# nas.net
KiCad netlist of a schematic drawn in EAGLE
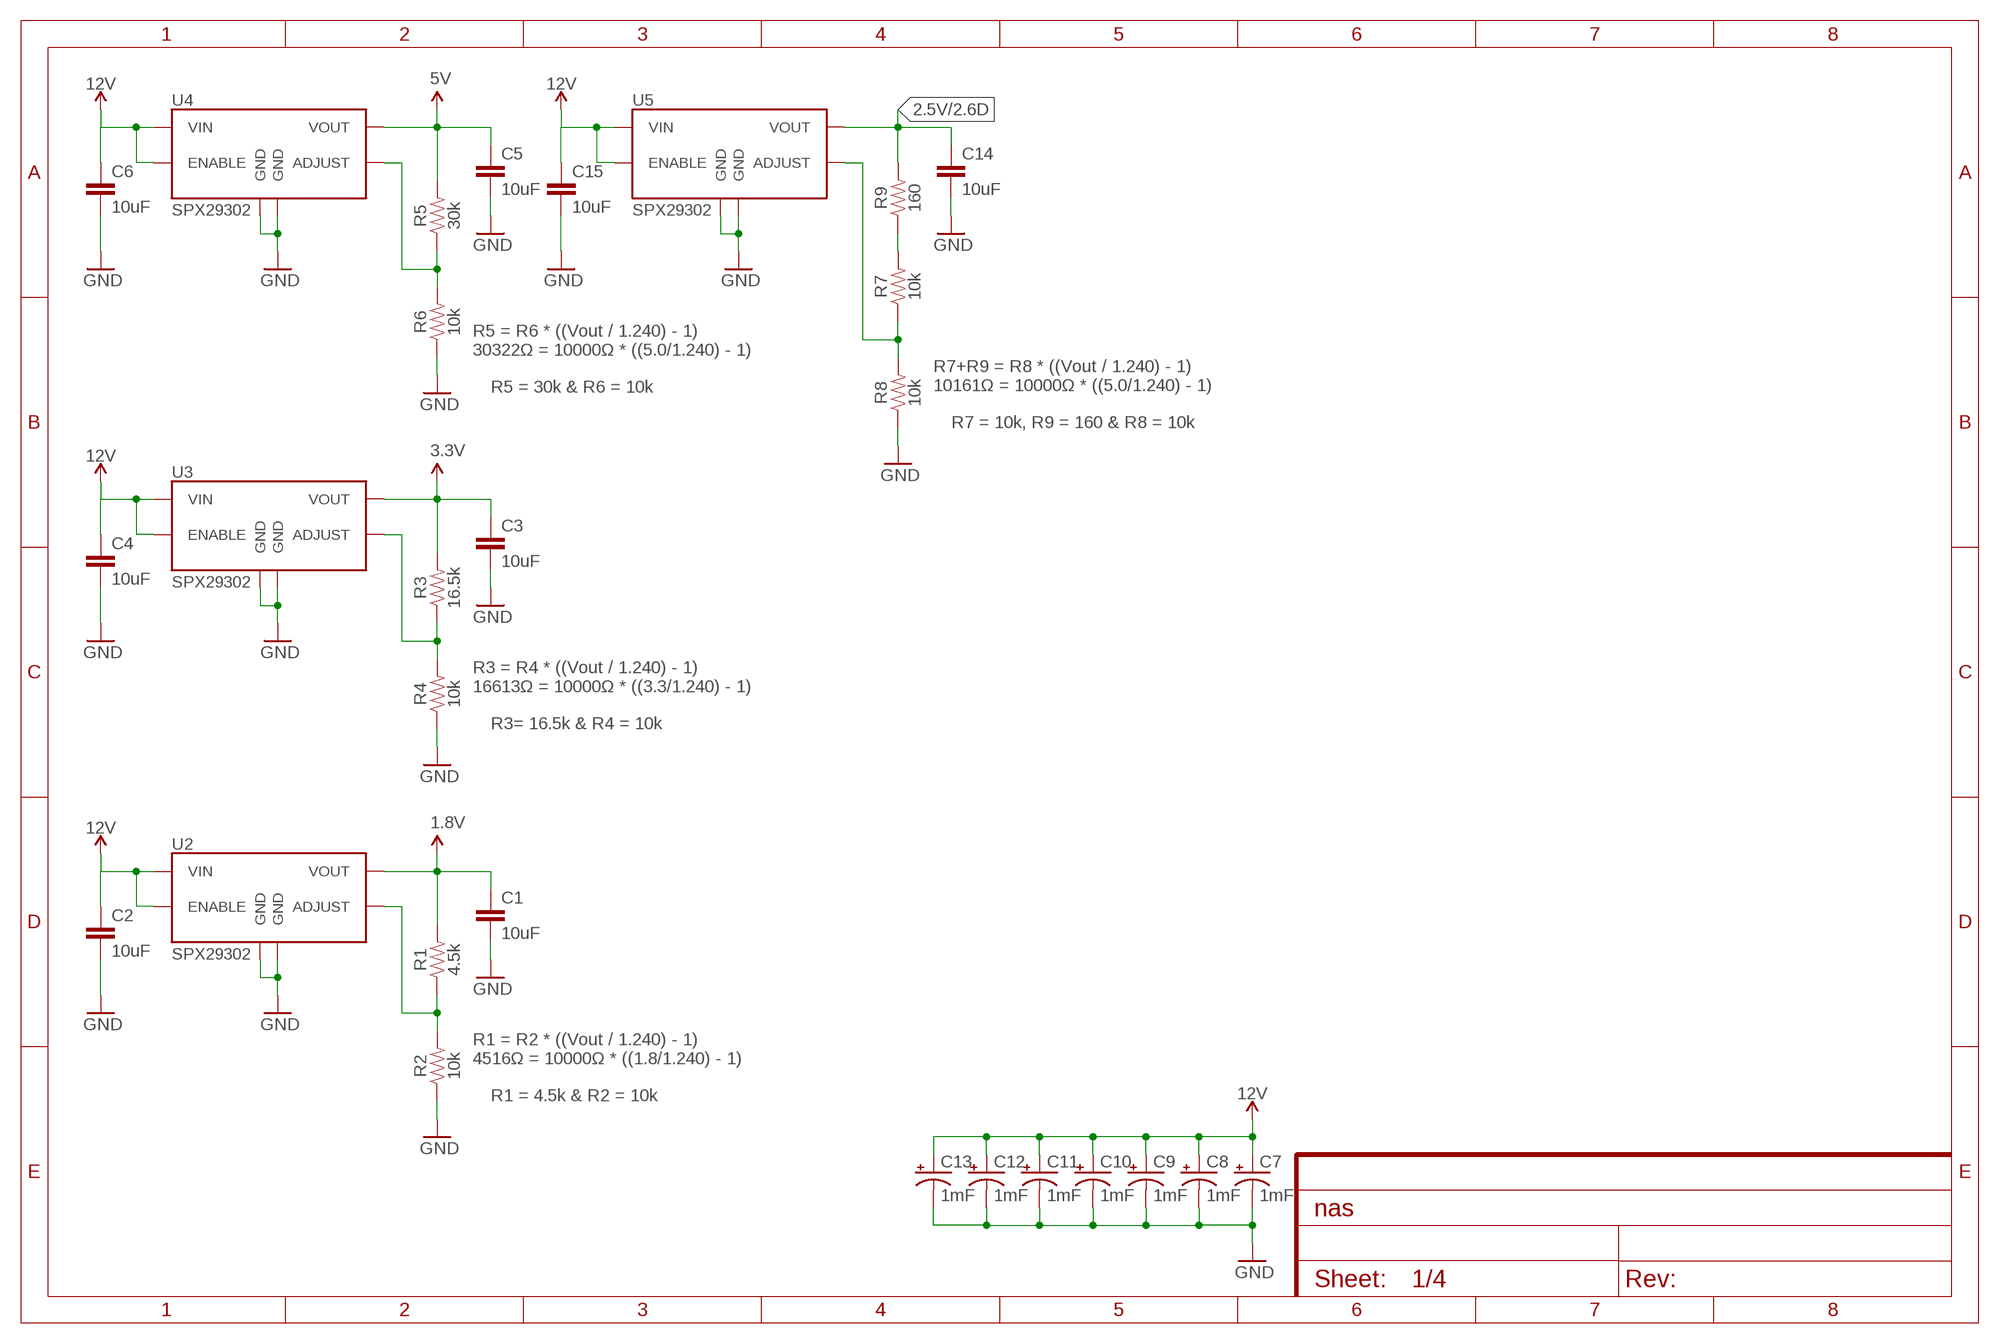
[diagram p0: schematic, sheet 1]
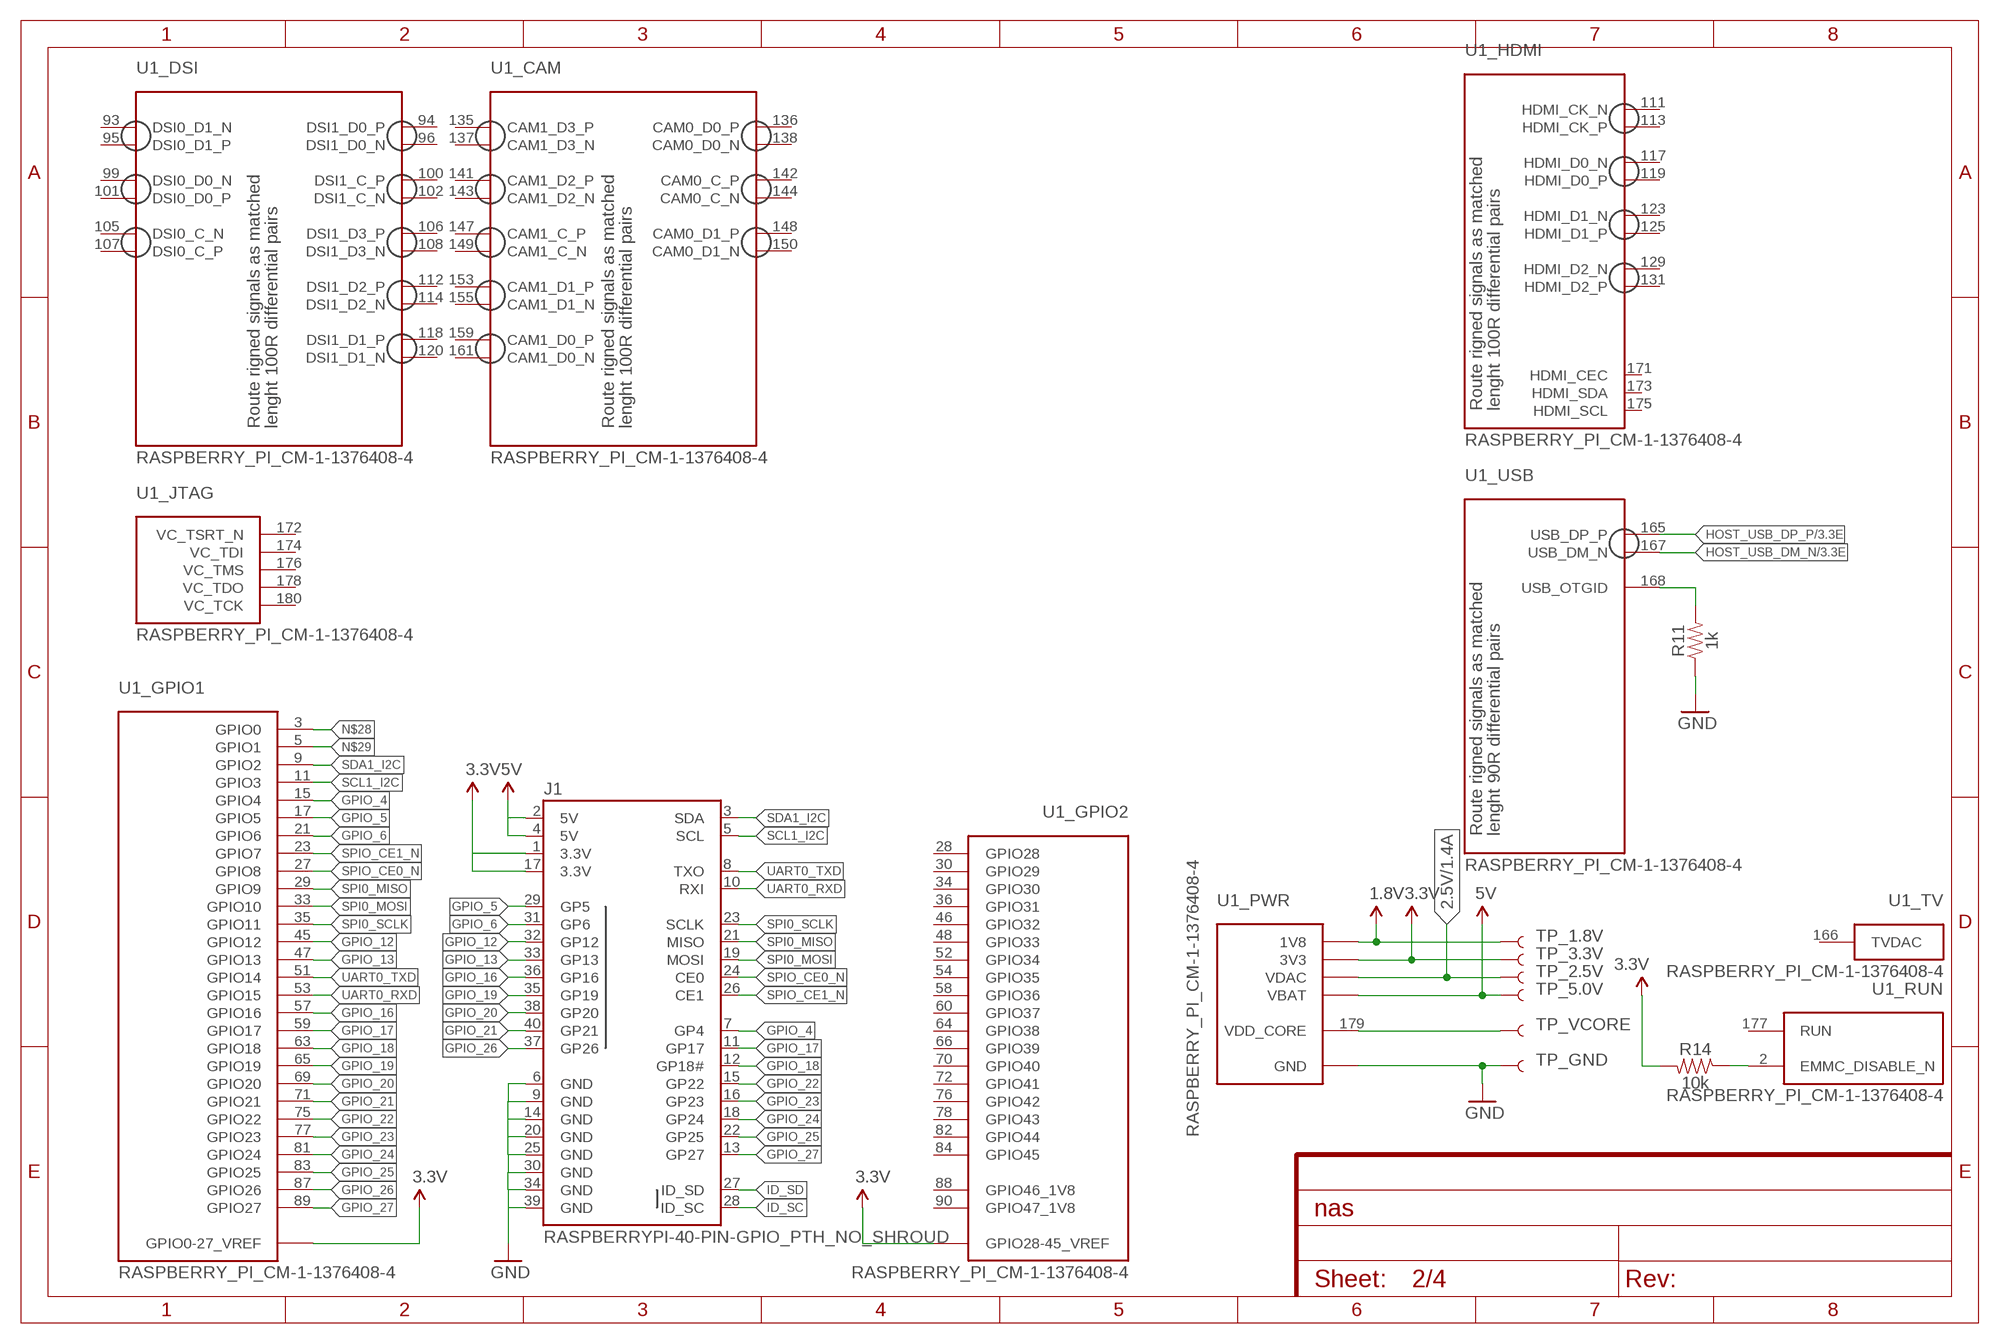
[diagram p1: schematic, sheet 2]
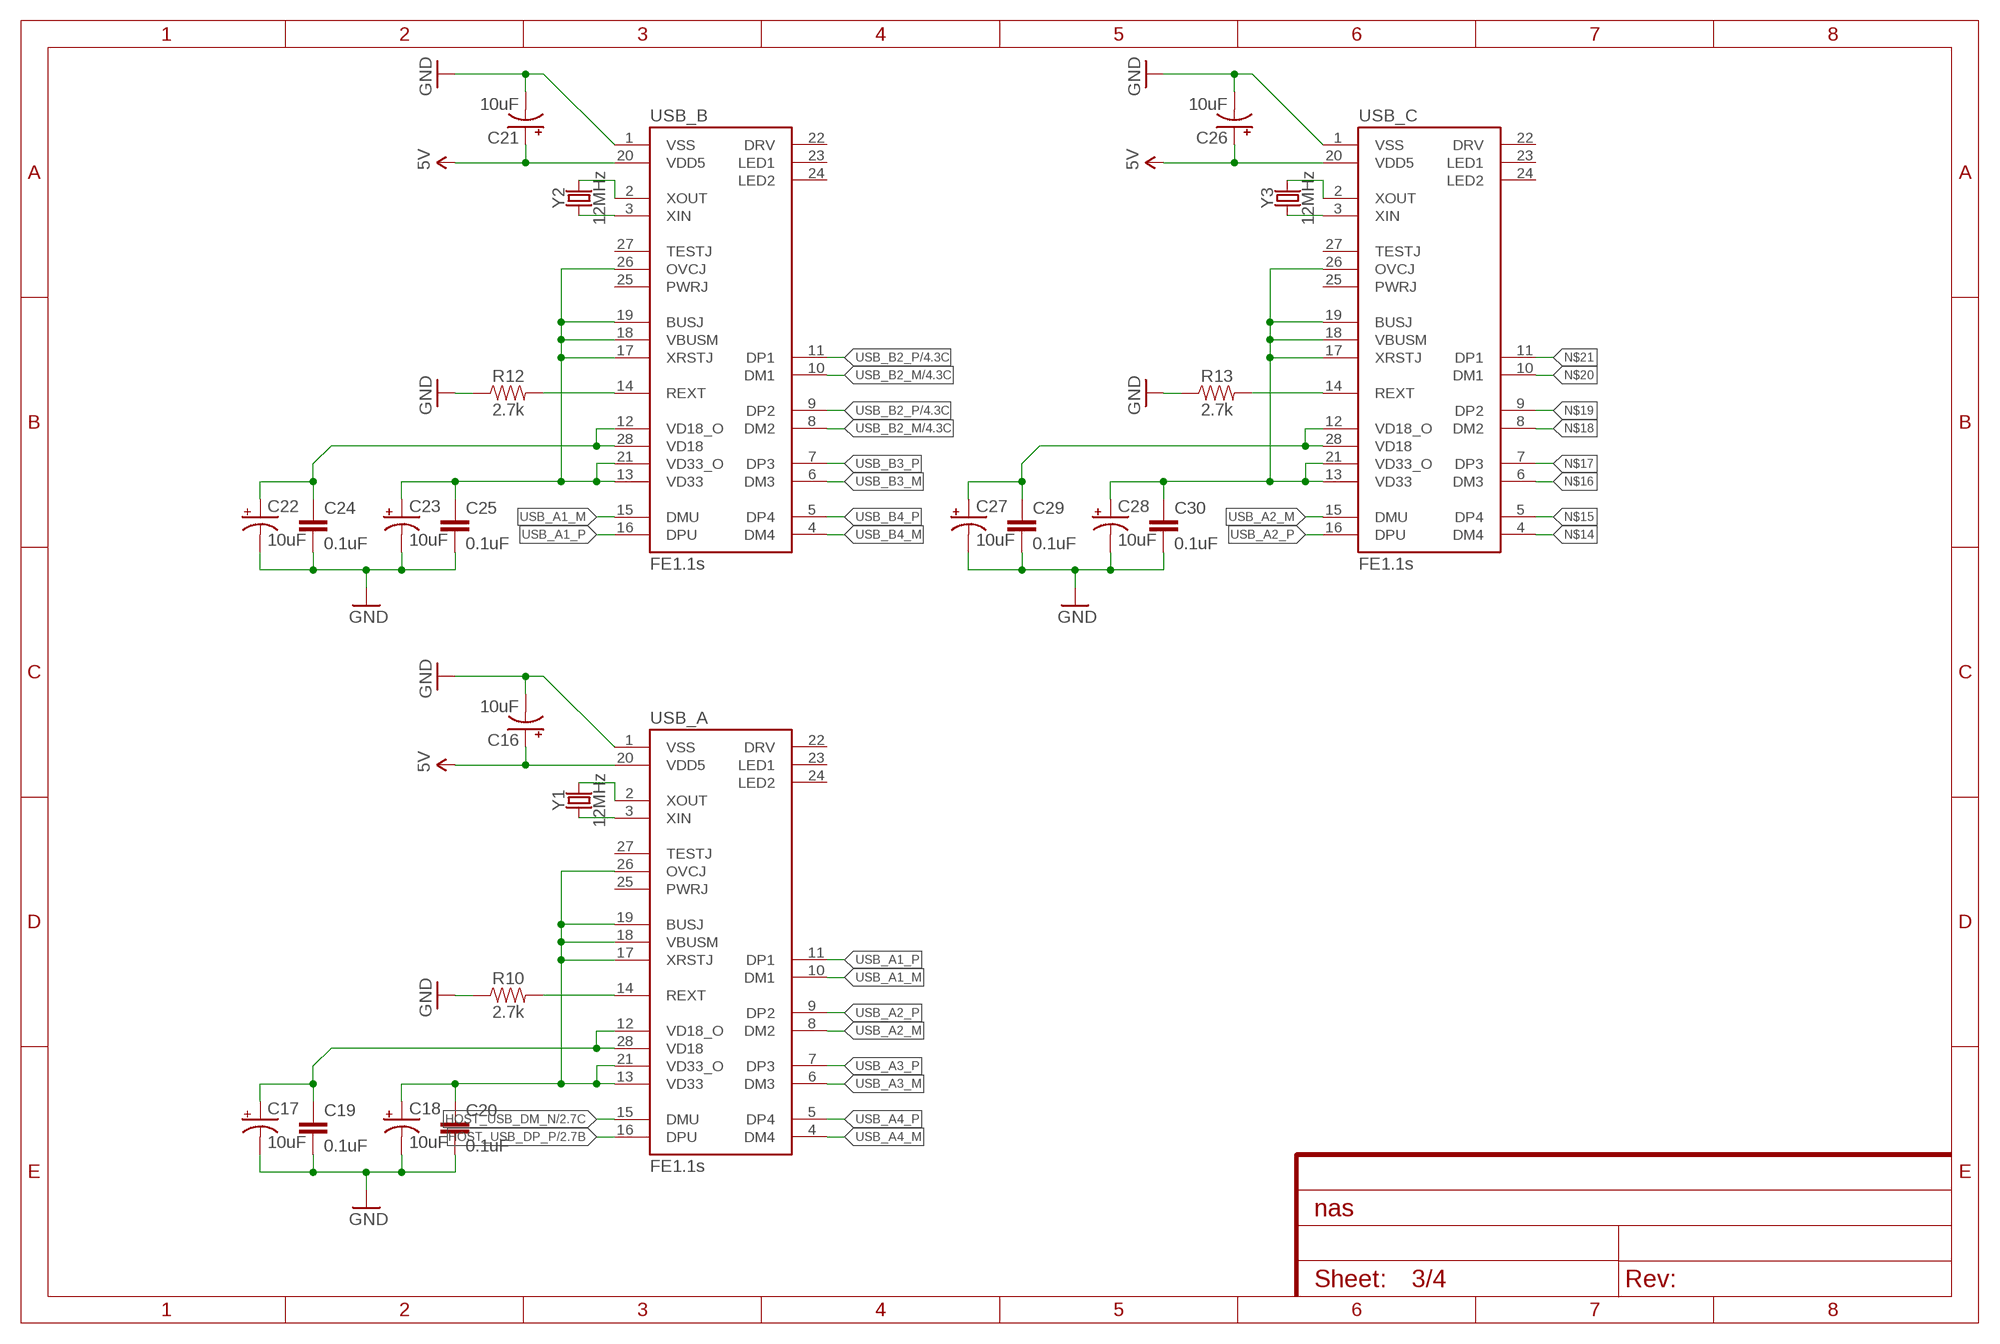
[diagram p2: schematic, sheet 3]
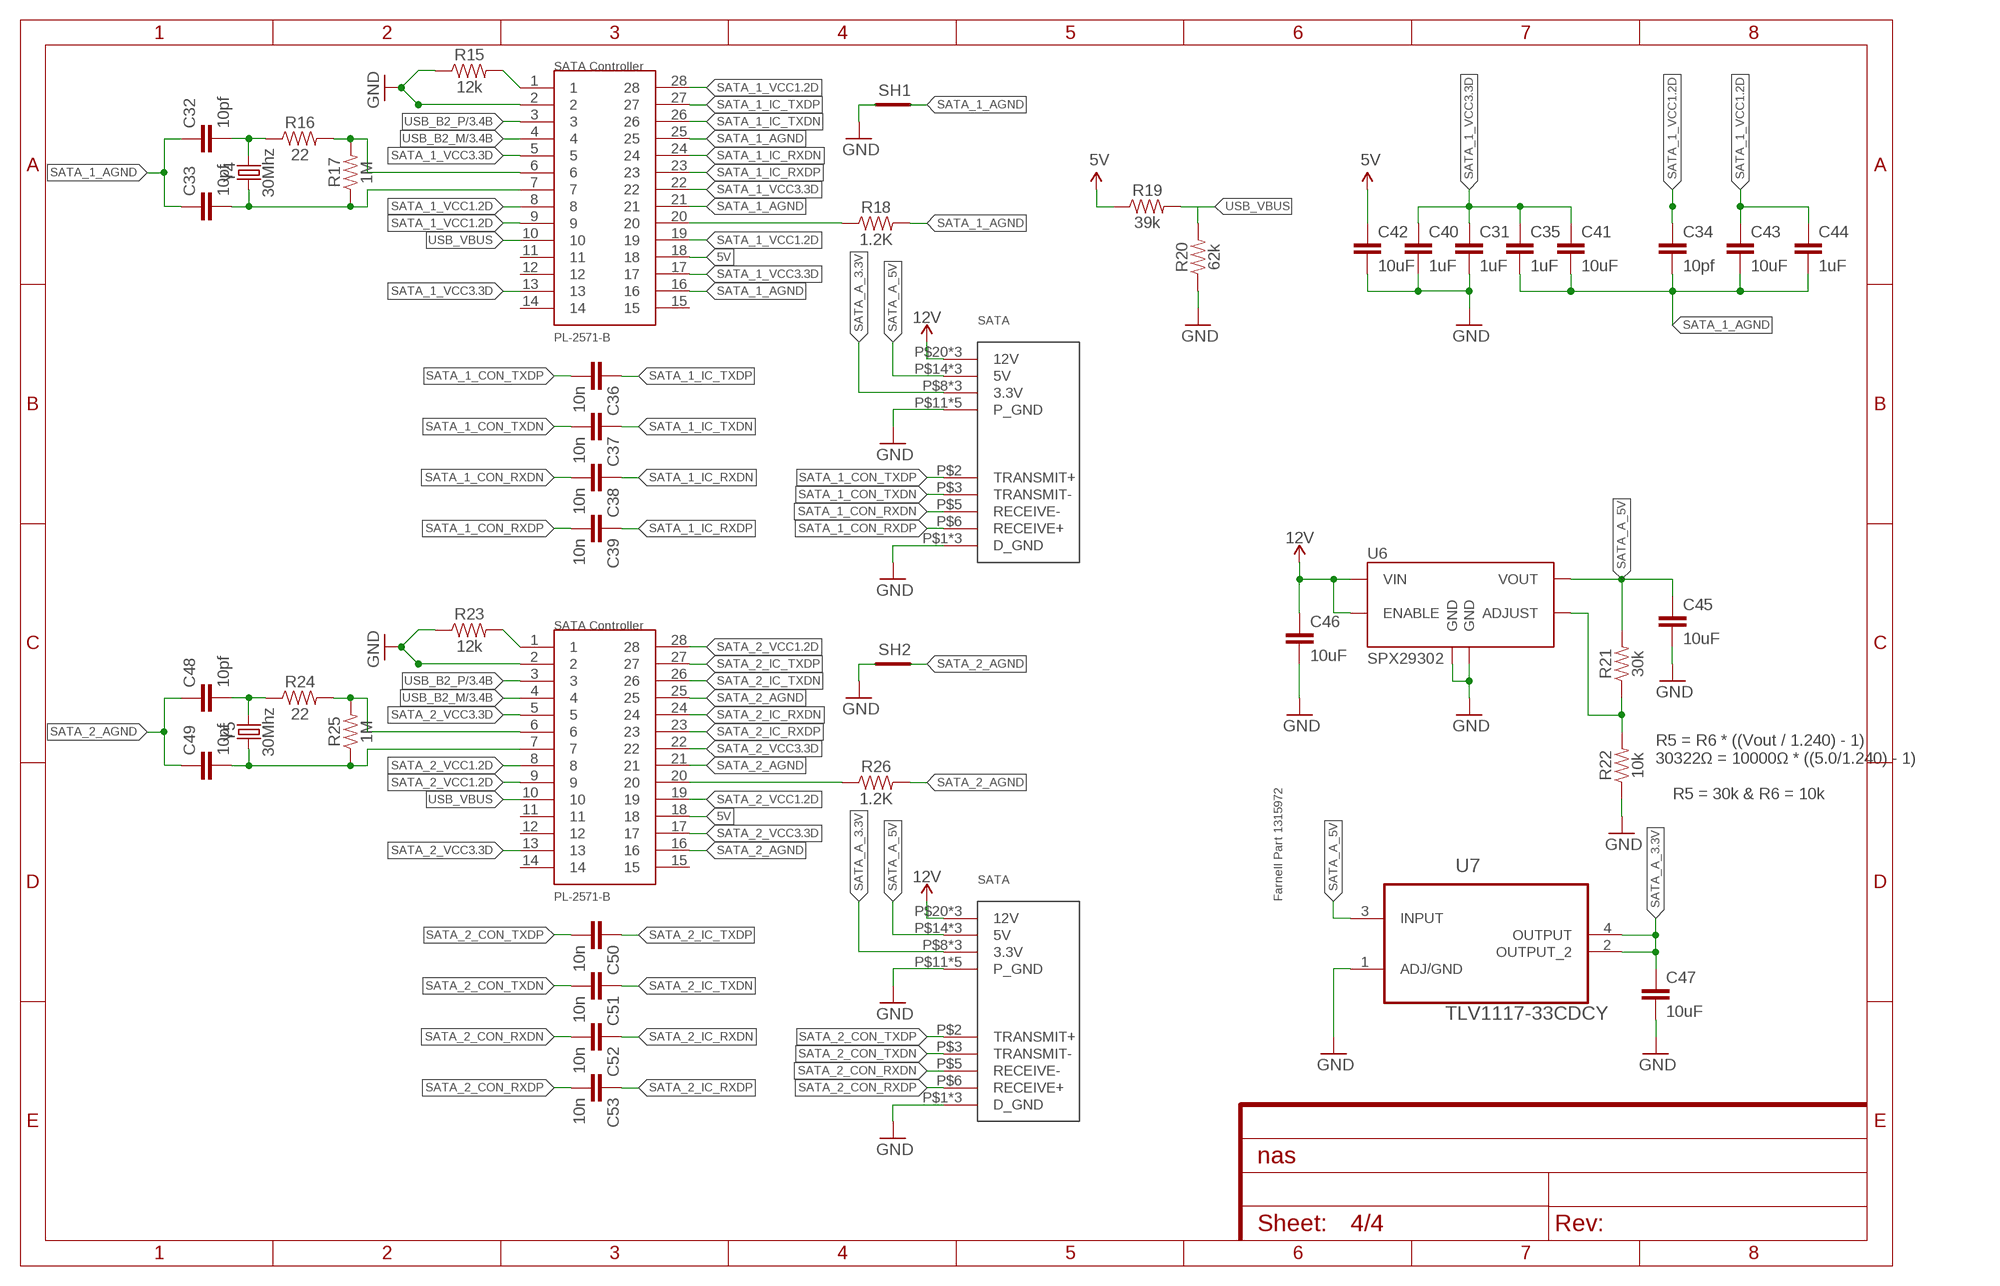
[diagram p3: schematic, sheet 4]

(export (version "E")
  (design (tool "Eeschema 10.0.6"))
  (components
    (comp (ref "J1")
      (value "RASPBERRYPI-40-PIN-GPIO_PTH_NO_SHROUD")
      (footprint "eagle-import:2X20")
      (libsource (lib "eagle-import") (part "RASPBERRYPI-40-PIN-GPIO_PTH_NO_SHROUD"))
    )
    (comp (ref "R11")
      (value "1k")
      (footprint "eagle-import:1206")
      (libsource (lib "eagle-import") (part "RESISTOR1206"))
    )
    (comp (ref "R14")
      (value "10k")
      (footprint "eagle-import:1206")
      (libsource (lib "eagle-import") (part "RESISTOR1206"))
    )
    (comp (ref "TP_1.8V")
      (value "TEST-POINT2")
      (footprint "eagle-import:PAD.02X.02")
      (libsource (lib "eagle-import") (part "TEST-POINT2"))
    )
    (comp (ref "TP_2.5V")
      (value "TEST-POINT2")
      (footprint "eagle-import:PAD.02X.02")
      (libsource (lib "eagle-import") (part "TEST-POINT2"))
    )
    (comp (ref "TP_3.3V")
      (value "TEST-POINT2")
      (footprint "eagle-import:PAD.02X.02")
      (libsource (lib "eagle-import") (part "TEST-POINT2"))
    )
    (comp (ref "TP_5.0V")
      (value "TEST-POINT2")
      (footprint "eagle-import:PAD.02X.02")
      (libsource (lib "eagle-import") (part "TEST-POINT2"))
    )
    (comp (ref "TP_GND")
      (value "TEST-POINT2")
      (footprint "eagle-import:PAD.02X.02")
      (libsource (lib "eagle-import") (part "TEST-POINT2"))
    )
    (comp (ref "TP_VCORE")
      (value "TEST-POINT2")
      (footprint "eagle-import:PAD.02X.02")
      (libsource (lib "eagle-import") (part "TEST-POINT2"))
    )
    (comp (ref "U1")
      (value "RASPBERRY_PI_CM-1-1376408-4")
      (footprint "eagle-import:1-1376408-4")
      (libsource (lib "eagle-import") (part "RASPBERRY_PI_CM-1-1376408-4"))
    )
    (comp (ref "C16")
      (value "10uF")
      (footprint "eagle-import:EIA3216")
      (libsource (lib "eagle-import") (part "10UF-POLAR-EIA3216-16V-10%(TANT)"))
    )
    (comp (ref "C17")
      (value "10uF")
      (footprint "eagle-import:EIA3216")
      (libsource (lib "eagle-import") (part "10UF-POLAR-EIA3216-16V-10%(TANT)"))
    )
    (comp (ref "C18")
      (value "10uF")
      (footprint "eagle-import:EIA3216")
      (libsource (lib "eagle-import") (part "10UF-POLAR-EIA3216-16V-10%(TANT)"))
    )
    (comp (ref "C19")
      (value "0.1uF")
      (footprint "eagle-import:1206")
      (libsource (lib "eagle-import") (part "10UF-1206-6.3V-20%"))
    )
    (comp (ref "C20")
      (value "0.1uF")
      (footprint "eagle-import:1206")
      (libsource (lib "eagle-import") (part "10UF-1206-6.3V-20%"))
    )
    (comp (ref "C21")
      (value "10uF")
      (footprint "eagle-import:EIA3216")
      (libsource (lib "eagle-import") (part "10UF-POLAR-EIA3216-16V-10%(TANT)"))
    )
    (comp (ref "C22")
      (value "10uF")
      (footprint "eagle-import:EIA3216")
      (libsource (lib "eagle-import") (part "10UF-POLAR-EIA3216-16V-10%(TANT)"))
    )
    (comp (ref "C23")
      (value "10uF")
      (footprint "eagle-import:EIA3216")
      (libsource (lib "eagle-import") (part "10UF-POLAR-EIA3216-16V-10%(TANT)"))
    )
    (comp (ref "C24")
      (value "0.1uF")
      (footprint "eagle-import:1206")
      (libsource (lib "eagle-import") (part "10UF-1206-6.3V-20%"))
    )
    (comp (ref "C25")
      (value "0.1uF")
      (footprint "eagle-import:1206")
      (libsource (lib "eagle-import") (part "10UF-1206-6.3V-20%"))
    )
    (comp (ref "C26")
      (value "10uF")
      (footprint "eagle-import:EIA3216")
      (libsource (lib "eagle-import") (part "10UF-POLAR-EIA3216-16V-10%(TANT)"))
    )
    (comp (ref "C27")
      (value "10uF")
      (footprint "eagle-import:EIA3216")
      (libsource (lib "eagle-import") (part "10UF-POLAR-EIA3216-16V-10%(TANT)"))
    )
    (comp (ref "C28")
      (value "10uF")
      (footprint "eagle-import:EIA3216")
      (libsource (lib "eagle-import") (part "10UF-POLAR-EIA3216-16V-10%(TANT)"))
    )
    (comp (ref "C29")
      (value "0.1uF")
      (footprint "eagle-import:1206")
      (libsource (lib "eagle-import") (part "10UF-1206-6.3V-20%"))
    )
    (comp (ref "C30")
      (value "0.1uF")
      (footprint "eagle-import:1206")
      (libsource (lib "eagle-import") (part "10UF-1206-6.3V-20%"))
    )
    (comp (ref "R10")
      (value "2.7k")
      (footprint "eagle-import:1206")
      (libsource (lib "eagle-import") (part "RESISTOR1206"))
    )
    (comp (ref "R12")
      (value "2.7k")
      (footprint "eagle-import:1206")
      (libsource (lib "eagle-import") (part "RESISTOR1206"))
    )
    (comp (ref "R13")
      (value "2.7k")
      (footprint "eagle-import:1206")
      (libsource (lib "eagle-import") (part "RESISTOR1206"))
    )
    (comp (ref "USB_A")
      (value "FE1.1S")
      (footprint "eagle-import:FE1.1S_SSOP-28")
      (libsource (lib "eagle-import") (part "FE1.1S"))
    )
    (comp (ref "USB_B")
      (value "FE1.1S")
      (footprint "eagle-import:FE1.1S_SSOP-28")
      (libsource (lib "eagle-import") (part "FE1.1S"))
    )
    (comp (ref "USB_C")
      (value "FE1.1S")
      (footprint "eagle-import:FE1.1S_SSOP-28")
      (libsource (lib "eagle-import") (part "FE1.1S"))
    )
    (comp (ref "Y1")
      (value "12MHz")
      (footprint "eagle-import:CRYSTAL-SMD-5X3.2-4PAD")
      (libsource (lib "eagle-import") (part "CRYSTAL-12MHZ{dblquote}"))
    )
    (comp (ref "Y2")
      (value "12MHz")
      (footprint "eagle-import:CRYSTAL-SMD-5X3.2-4PAD")
      (libsource (lib "eagle-import") (part "CRYSTAL-12MHZ{dblquote}"))
    )
    (comp (ref "Y3")
      (value "12MHz")
      (footprint "eagle-import:CRYSTAL-SMD-5X3.2-4PAD")
      (libsource (lib "eagle-import") (part "CRYSTAL-12MHZ{dblquote}"))
    )
    (comp (ref "C1")
      (value "10uF")
      (footprint "eagle-import:1206")
      (libsource (lib "eagle-import") (part "10UF-1206-6.3V-20%"))
    )
    (comp (ref "C2")
      (value "10uF")
      (footprint "eagle-import:1206")
      (libsource (lib "eagle-import") (part "10UF-1206-6.3V-20%"))
    )
    (comp (ref "C3")
      (value "10uF")
      (footprint "eagle-import:1206")
      (libsource (lib "eagle-import") (part "10UF-1206-6.3V-20%"))
    )
    (comp (ref "C4")
      (value "10uF")
      (footprint "eagle-import:1206")
      (libsource (lib "eagle-import") (part "10UF-1206-6.3V-20%"))
    )
    (comp (ref "C5")
      (value "10uF")
      (footprint "eagle-import:1206")
      (libsource (lib "eagle-import") (part "10UF-1206-6.3V-20%"))
    )
    (comp (ref "C6")
      (value "10uF")
      (footprint "eagle-import:1206")
      (libsource (lib "eagle-import") (part "10UF-1206-6.3V-20%"))
    )
    (comp (ref "C7")
      (value "1mF")
      (footprint "eagle-import:CPOL-RADIAL-5MM-10MM")
      (libsource (lib "eagle-import") (part "1000UF-RADIAL-5MM-25V-20%"))
    )
    (comp (ref "C8")
      (value "1mF")
      (footprint "eagle-import:CPOL-RADIAL-5MM-10MM")
      (libsource (lib "eagle-import") (part "1000UF-RADIAL-5MM-25V-20%"))
    )
    (comp (ref "C9")
      (value "1mF")
      (footprint "eagle-import:CPOL-RADIAL-5MM-10MM")
      (libsource (lib "eagle-import") (part "1000UF-RADIAL-5MM-25V-20%"))
    )
    (comp (ref "C10")
      (value "1mF")
      (footprint "eagle-import:CPOL-RADIAL-5MM-10MM")
      (libsource (lib "eagle-import") (part "1000UF-RADIAL-5MM-25V-20%"))
    )
    (comp (ref "C11")
      (value "1mF")
      (footprint "eagle-import:CPOL-RADIAL-5MM-10MM")
      (libsource (lib "eagle-import") (part "1000UF-RADIAL-5MM-25V-20%"))
    )
    (comp (ref "C12")
      (value "1mF")
      (footprint "eagle-import:CPOL-RADIAL-5MM-10MM")
      (libsource (lib "eagle-import") (part "1000UF-RADIAL-5MM-25V-20%"))
    )
    (comp (ref "C13")
      (value "1mF")
      (footprint "eagle-import:CPOL-RADIAL-5MM-10MM")
      (libsource (lib "eagle-import") (part "1000UF-RADIAL-5MM-25V-20%"))
    )
    (comp (ref "C14")
      (value "10uF")
      (footprint "eagle-import:1206")
      (libsource (lib "eagle-import") (part "10UF-1206-6.3V-20%"))
    )
    (comp (ref "C15")
      (value "10uF")
      (footprint "eagle-import:1206")
      (libsource (lib "eagle-import") (part "10UF-1206-6.3V-20%"))
    )
    (comp (ref "R1")
      (value "4.5k")
      (footprint "eagle-import:1206")
      (libsource (lib "eagle-import") (part "RESISTOR1206"))
    )
    (comp (ref "R2")
      (value "10k")
      (footprint "eagle-import:1206")
      (libsource (lib "eagle-import") (part "RESISTOR1206"))
    )
    (comp (ref "R3")
      (value "16.5k")
      (footprint "eagle-import:1206")
      (libsource (lib "eagle-import") (part "RESISTOR1206"))
    )
    (comp (ref "R4")
      (value "10k")
      (footprint "eagle-import:1206")
      (libsource (lib "eagle-import") (part "RESISTOR1206"))
    )
    (comp (ref "R5")
      (value "30k")
      (footprint "eagle-import:1206")
      (libsource (lib "eagle-import") (part "RESISTOR1206"))
    )
    (comp (ref "R6")
      (value "10k")
      (footprint "eagle-import:1206")
      (libsource (lib "eagle-import") (part "RESISTOR1206"))
    )
    (comp (ref "R7")
      (value "10k")
      (footprint "eagle-import:1206")
      (libsource (lib "eagle-import") (part "RESISTOR1206"))
    )
    (comp (ref "R8")
      (value "10k")
      (footprint "eagle-import:1206")
      (libsource (lib "eagle-import") (part "RESISTOR1206"))
    )
    (comp (ref "R9")
      (value "160")
      (footprint "eagle-import:1206")
      (libsource (lib "eagle-import") (part "RESISTOR1206"))
    )
    (comp (ref "U2")
      (value "SPX29302")
      (footprint "eagle-import:Q5-DD_SPX29300")
      (libsource (lib "eagle-import") (part "SPX29302"))
    )
    (comp (ref "U3")
      (value "SPX29302")
      (footprint "eagle-import:Q5-DD_SPX29300")
      (libsource (lib "eagle-import") (part "SPX29302"))
    )
    (comp (ref "U4")
      (value "SPX29302")
      (footprint "eagle-import:Q5-DD_SPX29300")
      (libsource (lib "eagle-import") (part "SPX29302"))
    )
    (comp (ref "U5")
      (value "SPX29302")
      (footprint "eagle-import:Q5-DD_SPX29300")
      (libsource (lib "eagle-import") (part "SPX29302"))
    )
    (comp (ref "C31")
      (value "1uF")
      (footprint "eagle-import:1206")
      (libsource (lib "eagle-import") (part "10UF-1206-6.3V-20%"))
    )
    (comp (ref "C32")
      (value "10pf")
      (footprint "eagle-import:1206")
      (libsource (lib "eagle-import") (part "10UF-1206-6.3V-20%"))
    )
    (comp (ref "C33")
      (value "10pf")
      (footprint "eagle-import:1206")
      (libsource (lib "eagle-import") (part "10UF-1206-6.3V-20%"))
    )
    (comp (ref "C34")
      (value "10pf")
      (footprint "eagle-import:1206")
      (libsource (lib "eagle-import") (part "10UF-1206-6.3V-20%"))
    )
    (comp (ref "C35")
      (value "1uF")
      (footprint "eagle-import:1206")
      (libsource (lib "eagle-import") (part "10UF-1206-6.3V-20%"))
    )
    (comp (ref "C36")
      (value "10n")
      (footprint "eagle-import:1206")
      (libsource (lib "eagle-import") (part "10UF-1206-6.3V-20%"))
    )
    (comp (ref "C37")
      (value "10n")
      (footprint "eagle-import:1206")
      (libsource (lib "eagle-import") (part "10UF-1206-6.3V-20%"))
    )
    (comp (ref "C38")
      (value "10n")
      (footprint "eagle-import:1206")
      (libsource (lib "eagle-import") (part "10UF-1206-6.3V-20%"))
    )
    (comp (ref "C39")
      (value "10n")
      (footprint "eagle-import:1206")
      (libsource (lib "eagle-import") (part "10UF-1206-6.3V-20%"))
    )
    (comp (ref "C40")
      (value "1uF")
      (footprint "eagle-import:1206")
      (libsource (lib "eagle-import") (part "10UF-1206-6.3V-20%"))
    )
    (comp (ref "C41")
      (value "10uF")
      (footprint "eagle-import:1206")
      (libsource (lib "eagle-import") (part "10UF-1206-6.3V-20%"))
    )
    (comp (ref "C42")
      (value "10uF")
      (footprint "eagle-import:1206")
      (libsource (lib "eagle-import") (part "10UF-1206-6.3V-20%"))
    )
    (comp (ref "C43")
      (value "10uF")
      (footprint "eagle-import:1206")
      (libsource (lib "eagle-import") (part "10UF-1206-6.3V-20%"))
    )
    (comp (ref "C44")
      (value "1uF")
      (footprint "eagle-import:1206")
      (libsource (lib "eagle-import") (part "10UF-1206-6.3V-20%"))
    )
    (comp (ref "C45")
      (value "10uF")
      (footprint "eagle-import:1206")
      (libsource (lib "eagle-import") (part "10UF-1206-6.3V-20%"))
    )
    (comp (ref "C46")
      (value "10uF")
      (footprint "eagle-import:1206")
      (libsource (lib "eagle-import") (part "10UF-1206-6.3V-20%"))
    )
    (comp (ref "C47")
      (value "10uF")
      (footprint "eagle-import:1206")
      (libsource (lib "eagle-import") (part "10UF-1206-6.3V-20%"))
    )
    (comp (ref "C48")
      (value "10pf")
      (footprint "eagle-import:1206")
      (libsource (lib "eagle-import") (part "10UF-1206-6.3V-20%"))
    )
    (comp (ref "C49")
      (value "10pf")
      (footprint "eagle-import:1206")
      (libsource (lib "eagle-import") (part "10UF-1206-6.3V-20%"))
    )
    (comp (ref "C50")
      (value "10n")
      (footprint "eagle-import:1206")
      (libsource (lib "eagle-import") (part "10UF-1206-6.3V-20%"))
    )
    (comp (ref "C51")
      (value "10n")
      (footprint "eagle-import:1206")
      (libsource (lib "eagle-import") (part "10UF-1206-6.3V-20%"))
    )
    (comp (ref "C52")
      (value "10n")
      (footprint "eagle-import:1206")
      (libsource (lib "eagle-import") (part "10UF-1206-6.3V-20%"))
    )
    (comp (ref "C53")
      (value "10n")
      (footprint "eagle-import:1206")
      (libsource (lib "eagle-import") (part "10UF-1206-6.3V-20%"))
    )
    (comp (ref "R15")
      (value "12k")
      (footprint "eagle-import:1206")
      (libsource (lib "eagle-import") (part "RESISTOR1206"))
    )
    (comp (ref "R16")
      (value "22")
      (footprint "eagle-import:1206")
      (libsource (lib "eagle-import") (part "RESISTOR1206"))
    )
    (comp (ref "R17")
      (value "1M")
      (footprint "eagle-import:1206")
      (libsource (lib "eagle-import") (part "RESISTOR1206"))
    )
    (comp (ref "R18")
      (value "1.2K")
      (footprint "eagle-import:1206")
      (libsource (lib "eagle-import") (part "RESISTOR1206"))
    )
    (comp (ref "R19")
      (value "39k")
      (footprint "eagle-import:1206")
      (libsource (lib "eagle-import") (part "RESISTOR1206"))
    )
    (comp (ref "R20")
      (value "62k")
      (footprint "eagle-import:1206")
      (libsource (lib "eagle-import") (part "RESISTOR1206"))
    )
    (comp (ref "R21")
      (value "30k")
      (footprint "eagle-import:1206")
      (libsource (lib "eagle-import") (part "RESISTOR1206"))
    )
    (comp (ref "R22")
      (value "10k")
      (footprint "eagle-import:1206")
      (libsource (lib "eagle-import") (part "RESISTOR1206"))
    )
    (comp (ref "R23")
      (value "12k")
      (footprint "eagle-import:1206")
      (libsource (lib "eagle-import") (part "RESISTOR1206"))
    )
    (comp (ref "R24")
      (value "22")
      (footprint "eagle-import:1206")
      (libsource (lib "eagle-import") (part "RESISTOR1206"))
    )
    (comp (ref "R25")
      (value "1M")
      (footprint "eagle-import:1206")
      (libsource (lib "eagle-import") (part "RESISTOR1206"))
    )
    (comp (ref "R26")
      (value "1.2K")
      (footprint "eagle-import:1206")
      (libsource (lib "eagle-import") (part "RESISTOR1206"))
    )
    (comp (ref "SH1")
      (value "SHORT-HT5")
      (footprint "eagle-import:SHORT_TOP-50")
      (libsource (lib "eagle-import") (part "SHORT-HT5"))
    )
    (comp (ref "SH2")
      (value "SHORT-HT5")
      (footprint "eagle-import:SHORT_TOP-50")
      (libsource (lib "eagle-import") (part "SHORT-HT5"))
    )
    (comp (ref "U$12")
      (value "PL-2571-B")
      (footprint "eagle-import:SSOP28DB")
      (libsource (lib "eagle-import") (part "SSOP28"))
    )
    (comp (ref "U$15")
      (value "SATA_POWER_AND_DATA")
      (footprint "eagle-import:3M-SATA-5622-1200-ML")
      (libsource (lib "eagle-import") (part "SATA_POWER_AND_DATA"))
    )
    (comp (ref "U$16")
      (value "PL-2571-B")
      (footprint "eagle-import:SSOP28DB")
      (libsource (lib "eagle-import") (part "SSOP28"))
    )
    (comp (ref "U$17")
      (value "SATA_POWER_AND_DATA")
      (footprint "eagle-import:3M-SATA-5622-1200-ML")
      (libsource (lib "eagle-import") (part "SATA_POWER_AND_DATA"))
    )
    (comp (ref "U6")
      (value "SPX29302")
      (footprint "eagle-import:Q5-DD_SPX29300")
      (libsource (lib "eagle-import") (part "SPX29302"))
    )
    (comp (ref "U7")
      (value "TLV1117-33CDCY")
      (footprint "eagle-import:SOT230P700X180-4N")
      (libsource (lib "eagle-import") (part "TLV1117-33CDCY"))
    )
    (comp (ref "Y4")
      (value "30Mhz")
      (footprint "eagle-import:CRYSTAL-SMD-5X3.2-4PAD")
      (libsource (lib "eagle-import") (part "CRYSTAL-12MHZ{dblquote}"))
    )
    (comp (ref "Y5")
      (value "30Mhz")
      (footprint "eagle-import:CRYSTAL-SMD-5X3.2-4PAD")
      (libsource (lib "eagle-import") (part "CRYSTAL-12MHZ{dblquote}"))
    )
  )
  (nets
    (net (code "1") (name "1.8V") (class "Default")
      (node (ref "C1") (pin "1") (pinfunction "1_1") (pintype "passive"))
      (node (ref "R1") (pin "2") (pinfunction "2_2") (pintype "passive"))
      (node (ref "TP_1.8V") (pin "P$1") (pinfunction "1_P$1") (pintype "bidirectional"))
      (node (ref "U1") (pin "183") (pinfunction "1V8_183") (pintype "bidirectional"))
      (node (ref "U1") (pin "184") (pinfunction "1V8_184") (pintype "bidirectional"))
      (node (ref "U1") (pin "185") (pinfunction "1V8_185") (pintype "bidirectional"))
      (node (ref "U1") (pin "186") (pinfunction "1V8_186") (pintype "bidirectional"))
      (node (ref "U2") (pin "4") (pinfunction "VOUT_4") (pintype "bidirectional"))
    )
    (net (code "2") (name "2.5V") (class "Default")
      (node (ref "C14") (pin "1") (pinfunction "1_1") (pintype "passive"))
      (node (ref "R9") (pin "2") (pinfunction "2_2") (pintype "passive"))
      (node (ref "TP_2.5V") (pin "P$1") (pinfunction "1_P$1") (pintype "bidirectional"))
      (node (ref "U1") (pin "189") (pinfunction "VDAC_189") (pintype "bidirectional"))
      (node (ref "U1") (pin "190") (pinfunction "VDAC_190") (pintype "bidirectional"))
      (node (ref "U5") (pin "4") (pinfunction "VOUT_4") (pintype "bidirectional"))
    )
    (net (code "3") (name "3.3V") (class "Default")
      (node (ref "C3") (pin "1") (pinfunction "1_1") (pintype "passive"))
      (node (ref "J1") (pin "1") (pinfunction "3.3V_1") (pintype "power_in"))
      (node (ref "J1") (pin "17") (pinfunction "3.3V_17") (pintype "power_in"))
      (node (ref "R14") (pin "2") (pinfunction "2_2") (pintype "passive"))
      (node (ref "R3") (pin "2") (pinfunction "2_2") (pintype "passive"))
      (node (ref "TP_3.3V") (pin "P$1") (pinfunction "1_P$1") (pintype "bidirectional"))
      (node (ref "U1") (pin "191") (pinfunction "3V3_191") (pintype "bidirectional"))
      (node (ref "U1") (pin "192") (pinfunction "3V3_192") (pintype "bidirectional"))
      (node (ref "U1") (pin "193") (pinfunction "3V3_193") (pintype "bidirectional"))
      (node (ref "U1") (pin "194") (pinfunction "3V3_194") (pintype "bidirectional"))
      (node (ref "U1") (pin "39") (pinfunction "GPIO0-27_VREF_39") (pintype "bidirectional"))
      (node (ref "U1") (pin "40") (pinfunction "GPIO0-27_VREF_40") (pintype "bidirectional"))
      (node (ref "U1") (pin "41") (pinfunction "GPIO28-45_VREF_41") (pintype "bidirectional"))
      (node (ref "U1") (pin "42") (pinfunction "GPIO28-45_VREF_42") (pintype "bidirectional"))
      (node (ref "U3") (pin "4") (pinfunction "VOUT_4") (pintype "bidirectional"))
    )
    (net (code "4") (name "5V") (class "Default")
      (node (ref "C16") (pin "+") (pinfunction "+_+") (pintype "passive"))
      (node (ref "C21") (pin "+") (pinfunction "+_+") (pintype "passive"))
      (node (ref "C26") (pin "+") (pinfunction "+_+") (pintype "passive"))
      (node (ref "C42") (pin "1") (pinfunction "1_1") (pintype "passive"))
      (node (ref "C5") (pin "1") (pinfunction "1_1") (pintype "passive"))
      (node (ref "J1") (pin "2") (pinfunction "5V_2") (pintype "power_in"))
      (node (ref "J1") (pin "4") (pinfunction "5V_4") (pintype "power_in"))
      (node (ref "R19") (pin "1") (pinfunction "1_1") (pintype "passive"))
      (node (ref "R5") (pin "2") (pinfunction "2_2") (pintype "passive"))
      (node (ref "TP_5.0V") (pin "P$1") (pinfunction "1_P$1") (pintype "bidirectional"))
      (node (ref "U$12") (pin "18") (pinfunction "18_18") (pintype "bidirectional"))
      (node (ref "U$16") (pin "18") (pinfunction "18_18") (pintype "bidirectional"))
      (node (ref "U1") (pin "197") (pinfunction "VBAT_197") (pintype "bidirectional"))
      (node (ref "U1") (pin "198") (pinfunction "VBAT_198") (pintype "bidirectional"))
      (node (ref "U1") (pin "199") (pinfunction "VBAT_199") (pintype "bidirectional"))
      (node (ref "U1") (pin "200") (pinfunction "VBAT_200") (pintype "bidirectional"))
      (node (ref "U4") (pin "4") (pinfunction "VOUT_4") (pintype "bidirectional"))
      (node (ref "USB_A") (pin "20") (pinfunction "VDD5_20") (pintype "bidirectional"))
      (node (ref "USB_B") (pin "20") (pinfunction "VDD5_20") (pintype "bidirectional"))
      (node (ref "USB_C") (pin "20") (pinfunction "VDD5_20") (pintype "bidirectional"))
    )
    (net (code "5") (name "12V") (class "Default")
      (node (ref "C10") (pin "+") (pinfunction "+_+") (pintype "passive"))
      (node (ref "C11") (pin "+") (pinfunction "+_+") (pintype "passive"))
      (node (ref "C12") (pin "+") (pinfunction "+_+") (pintype "passive"))
      (node (ref "C13") (pin "+") (pinfunction "+_+") (pintype "passive"))
      (node (ref "C15") (pin "1") (pinfunction "1_1") (pintype "passive"))
      (node (ref "C2") (pin "1") (pinfunction "1_1") (pintype "passive"))
      (node (ref "C4") (pin "1") (pinfunction "1_1") (pintype "passive"))
      (node (ref "C46") (pin "1") (pinfunction "1_1") (pintype "passive"))
      (node (ref "C6") (pin "1") (pinfunction "1_1") (pintype "passive"))
      (node (ref "C7") (pin "+") (pinfunction "+_+") (pintype "passive"))
      (node (ref "C8") (pin "+") (pinfunction "+_+") (pintype "passive"))
      (node (ref "C9") (pin "+") (pinfunction "+_+") (pintype "passive"))
      (node (ref "U$15") (pin "P$20") (pinfunction "12V_P$20") (pintype "bidirectional"))
      (node (ref "U$15") (pin "P$21") (pinfunction "12V_P$21") (pintype "bidirectional"))
      (node (ref "U$15") (pin "P$22") (pinfunction "12V_P$22") (pintype "bidirectional"))
      (node (ref "U$17") (pin "P$20") (pinfunction "12V_P$20") (pintype "bidirectional"))
      (node (ref "U$17") (pin "P$21") (pinfunction "12V_P$21") (pintype "bidirectional"))
      (node (ref "U$17") (pin "P$22") (pinfunction "12V_P$22") (pintype "bidirectional"))
      (node (ref "U2") (pin "1") (pinfunction "ENABLE_1") (pintype "bidirectional"))
      (node (ref "U2") (pin "2") (pinfunction "VIN_2") (pintype "bidirectional"))
      (node (ref "U3") (pin "1") (pinfunction "ENABLE_1") (pintype "bidirectional"))
      (node (ref "U3") (pin "2") (pinfunction "VIN_2") (pintype "bidirectional"))
      (node (ref "U4") (pin "1") (pinfunction "ENABLE_1") (pintype "bidirectional"))
      (node (ref "U4") (pin "2") (pinfunction "VIN_2") (pintype "bidirectional"))
      (node (ref "U5") (pin "1") (pinfunction "ENABLE_1") (pintype "bidirectional"))
      (node (ref "U5") (pin "2") (pinfunction "VIN_2") (pintype "bidirectional"))
      (node (ref "U6") (pin "1") (pinfunction "ENABLE_1") (pintype "bidirectional"))
      (node (ref "U6") (pin "2") (pinfunction "VIN_2") (pintype "bidirectional"))
    )
    (net (code "6") (name "GND") (class "Default")
      (node (ref "C1") (pin "2") (pinfunction "2_2") (pintype "passive"))
      (node (ref "C10") (pin "-") (pinfunction "-_-") (pintype "passive"))
      (node (ref "C11") (pin "-") (pinfunction "-_-") (pintype "passive"))
      (node (ref "C12") (pin "-") (pinfunction "-_-") (pintype "passive"))
      (node (ref "C13") (pin "-") (pinfunction "-_-") (pintype "passive"))
      (node (ref "C14") (pin "2") (pinfunction "2_2") (pintype "passive"))
      (node (ref "C15") (pin "2") (pinfunction "2_2") (pintype "passive"))
      (node (ref "C16") (pin "-") (pinfunction "-_-") (pintype "passive"))
      (node (ref "C17") (pin "-") (pinfunction "-_-") (pintype "passive"))
      (node (ref "C18") (pin "-") (pinfunction "-_-") (pintype "passive"))
      (node (ref "C19") (pin "2") (pinfunction "2_2") (pintype "passive"))
      (node (ref "C2") (pin "2") (pinfunction "2_2") (pintype "passive"))
      (node (ref "C20") (pin "2") (pinfunction "2_2") (pintype "passive"))
      (node (ref "C21") (pin "-") (pinfunction "-_-") (pintype "passive"))
      (node (ref "C22") (pin "-") (pinfunction "-_-") (pintype "passive"))
      (node (ref "C23") (pin "-") (pinfunction "-_-") (pintype "passive"))
      (node (ref "C24") (pin "2") (pinfunction "2_2") (pintype "passive"))
      (node (ref "C25") (pin "2") (pinfunction "2_2") (pintype "passive"))
      (node (ref "C26") (pin "-") (pinfunction "-_-") (pintype "passive"))
      (node (ref "C27") (pin "-") (pinfunction "-_-") (pintype "passive"))
      (node (ref "C28") (pin "-") (pinfunction "-_-") (pintype "passive"))
      (node (ref "C29") (pin "2") (pinfunction "2_2") (pintype "passive"))
      (node (ref "C3") (pin "2") (pinfunction "2_2") (pintype "passive"))
      (node (ref "C30") (pin "2") (pinfunction "2_2") (pintype "passive"))
      (node (ref "C31") (pin "2") (pinfunction "2_2") (pintype "passive"))
      (node (ref "C4") (pin "2") (pinfunction "2_2") (pintype "passive"))
      (node (ref "C40") (pin "2") (pinfunction "2_2") (pintype "passive"))
      (node (ref "C42") (pin "2") (pinfunction "2_2") (pintype "passive"))
      (node (ref "C45") (pin "2") (pinfunction "2_2") (pintype "passive"))
      (node (ref "C46") (pin "2") (pinfunction "2_2") (pintype "passive"))
      (node (ref "C47") (pin "2") (pinfunction "2_2") (pintype "passive"))
      (node (ref "C5") (pin "2") (pinfunction "2_2") (pintype "passive"))
      (node (ref "C6") (pin "2") (pinfunction "2_2") (pintype "passive"))
      (node (ref "C7") (pin "-") (pinfunction "-_-") (pintype "passive"))
      (node (ref "C8") (pin "-") (pinfunction "-_-") (pintype "passive"))
      (node (ref "C9") (pin "-") (pinfunction "-_-") (pintype "passive"))
      (node (ref "J1") (pin "14") (pinfunction "GND_14") (pintype "power_in"))
      (node (ref "J1") (pin "20") (pinfunction "GND_20") (pintype "power_in"))
      (node (ref "J1") (pin "25") (pinfunction "GND_25") (pintype "power_in"))
      (node (ref "J1") (pin "30") (pinfunction "GND_30") (pintype "power_in"))
      (node (ref "J1") (pin "34") (pinfunction "GND_34") (pintype "power_in"))
      (node (ref "J1") (pin "39") (pinfunction "GND_39") (pintype "power_in"))
      (node (ref "J1") (pin "6") (pinfunction "GND_6") (pintype "power_in"))
      (node (ref "J1") (pin "9") (pinfunction "GND_9") (pintype "power_in"))
      (node (ref "R10") (pin "1") (pinfunction "1_1") (pintype "passive"))
      (node (ref "R11") (pin "1") (pinfunction "1_1") (pintype "passive"))
      (node (ref "R12") (pin "1") (pinfunction "1_1") (pintype "passive"))
      (node (ref "R13") (pin "1") (pinfunction "1_1") (pintype "passive"))
      (node (ref "R15") (pin "1") (pinfunction "1_1") (pintype "passive"))
      (node (ref "R2") (pin "1") (pinfunction "1_1") (pintype "passive"))
      (node (ref "R20") (pin "1") (pinfunction "1_1") (pintype "passive"))
      (node (ref "R22") (pin "1") (pinfunction "1_1") (pintype "passive"))
      (node (ref "R23") (pin "1") (pinfunction "1_1") (pintype "passive"))
      (node (ref "R4") (pin "1") (pinfunction "1_1") (pintype "passive"))
      (node (ref "R6") (pin "1") (pinfunction "1_1") (pintype "passive"))
      (node (ref "R8") (pin "1") (pinfunction "1_1") (pintype "passive"))
      (node (ref "SH1") (pin "1") (pinfunction "P$1_1") (pintype "bidirectional"))
      (node (ref "SH2") (pin "1") (pinfunction "P$1_1") (pintype "bidirectional"))
      (node (ref "TP_GND") (pin "P$1") (pinfunction "1_P$1") (pintype "bidirectional"))
      (node (ref "U$12") (pin "2") (pinfunction "2_2") (pintype "bidirectional"))
      (node (ref "U$15") (pin "P$1") (pinfunction "D_GND_P$1") (pintype "bidirectional"))
      (node (ref "U$15") (pin "P$11") (pinfunction "P_GND_P$11") (pintype "bidirectional"))
      (node (ref "U$15") (pin "P$12") (pinfunction "P_GND_P$12") (pintype "bidirectional"))
      (node (ref "U$15") (pin "P$13") (pinfunction "P_GND_P$13") (pintype "bidirectional"))
      (node (ref "U$15") (pin "P$17") (pinfunction "P_GND_P$17") (pintype "bidirectional"))
      (node (ref "U$15") (pin "P$19") (pinfunction "P_GND_P$19") (pintype "bidirectional"))
      (node (ref "U$15") (pin "P$4") (pinfunction "D_GND_P$4") (pintype "bidirectional"))
      (node (ref "U$15") (pin "P$7") (pinfunction "D_GND_P$7") (pintype "bidirectional"))
      (node (ref "U$16") (pin "2") (pinfunction "2_2") (pintype "bidirectional"))
      (node (ref "U$17") (pin "P$1") (pinfunction "D_GND_P$1") (pintype "bidirectional"))
      (node (ref "U$17") (pin "P$11") (pinfunction "P_GND_P$11") (pintype "bidirectional"))
      (node (ref "U$17") (pin "P$12") (pinfunction "P_GND_P$12") (pintype "bidirectional"))
      (node (ref "U$17") (pin "P$13") (pinfunction "P_GND_P$13") (pintype "bidirectional"))
      (node (ref "U$17") (pin "P$17") (pinfunction "P_GND_P$17") (pintype "bidirectional"))
      (node (ref "U$17") (pin "P$19") (pinfunction "P_GND_P$19") (pintype "bidirectional"))
      (node (ref "U$17") (pin "P$4") (pinfunction "D_GND_P$4") (pintype "bidirectional"))
      (node (ref "U$17") (pin "P$7") (pinfunction "D_GND_P$7") (pintype "bidirectional"))
      (node (ref "U1") (pin "1") (pinfunction "GND_1") (pintype "bidirectional"))
      (node (ref "U1") (pin "103") (pinfunction "GND_103") (pintype "bidirectional"))
      (node (ref "U1") (pin "104") (pinfunction "GND_104") (pintype "bidirectional"))
      (node (ref "U1") (pin "109") (pinfunction "GND_109") (pintype "bidirectional"))
      (node (ref "U1") (pin "110") (pinfunction "GND_110") (pintype "bidirectional"))
      (node (ref "U1") (pin "115") (pinfunction "GND_115") (pintype "bidirectional"))
      (node (ref "U1") (pin "116") (pinfunction "GND_116") (pintype "bidirectional"))
      (node (ref "U1") (pin "121") (pinfunction "GND_121") (pintype "bidirectional"))
      (node (ref "U1") (pin "122") (pinfunction "GND_122") (pintype "bidirectional"))
      (node (ref "U1") (pin "127") (pinfunction "GND_127") (pintype "bidirectional"))
      (node (ref "U1") (pin "13") (pinfunction "GND_13") (pintype "bidirectional"))
      (node (ref "U1") (pin "133") (pinfunction "GND_133") (pintype "bidirectional"))
      (node (ref "U1") (pin "134") (pinfunction "GND_134") (pintype "bidirectional"))
      (node (ref "U1") (pin "139") (pinfunction "GND_139") (pintype "bidirectional"))
      (node (ref "U1") (pin "140") (pinfunction "GND_140") (pintype "bidirectional"))
      (node (ref "U1") (pin "145") (pinfunction "GND_145") (pintype "bidirectional"))
      (node (ref "U1") (pin "146") (pinfunction "GND_146") (pintype "bidirectional"))
      (node (ref "U1") (pin "151") (pinfunction "GND_151") (pintype "bidirectional"))
      (node (ref "U1") (pin "152") (pinfunction "GND_152") (pintype "bidirectional"))
      (node (ref "U1") (pin "157") (pinfunction "GND_157") (pintype "bidirectional"))
      (node (ref "U1") (pin "163") (pinfunction "GND_163") (pintype "bidirectional"))
      (node (ref "U1") (pin "164") (pinfunction "GND_164") (pintype "bidirectional"))
      (node (ref "U1") (pin "169") (pinfunction "GND_169") (pintype "bidirectional"))
      (node (ref "U1") (pin "170") (pinfunction "GND_170") (pintype "bidirectional"))
      (node (ref "U1") (pin "181") (pinfunction "GND_181") (pintype "bidirectional"))
      (node (ref "U1") (pin "182") (pinfunction "GND_182") (pintype "bidirectional"))
      (node (ref "U1") (pin "187") (pinfunction "GND_187") (pintype "bidirectional"))
      (node (ref "U1") (pin "188") (pinfunction "GND_188") (pintype "bidirectional"))
      (node (ref "U1") (pin "19") (pinfunction "GND_19") (pintype "bidirectional"))
      (node (ref "U1") (pin "195") (pinfunction "GND_195") (pintype "bidirectional"))
      (node (ref "U1") (pin "196") (pinfunction "GND_196") (pintype "bidirectional"))
      (node (ref "U1") (pin "25") (pinfunction "GND_25") (pintype "bidirectional"))
      (node (ref "U1") (pin "26") (pinfunction "GND_26") (pintype "bidirectional"))
      (node (ref "U1") (pin "31") (pinfunction "GND_31") (pintype "bidirectional"))
      (node (ref "U1") (pin "32") (pinfunction "GND_32") (pintype "bidirectional"))
      (node (ref "U1") (pin "37") (pinfunction "GND_37") (pintype "bidirectional"))
      (node (ref "U1") (pin "38") (pinfunction "GND_38") (pintype "bidirectional"))
      (node (ref "U1") (pin "43") (pinfunction "GND_43") (pintype "bidirectional"))
      (node (ref "U1") (pin "44") (pinfunction "GND_44") (pintype "bidirectional"))
      (node (ref "U1") (pin "49") (pinfunction "GND_49") (pintype "bidirectional"))
      (node (ref "U1") (pin "50") (pinfunction "GND_50") (pintype "bidirectional"))
      (node (ref "U1") (pin "55") (pinfunction "GND_55") (pintype "bidirectional"))
      (node (ref "U1") (pin "56") (pinfunction "GND_56") (pintype "bidirectional"))
      (node (ref "U1") (pin "61") (pinfunction "GND_61") (pintype "bidirectional"))
      (node (ref "U1") (pin "62") (pinfunction "GND_62") (pintype "bidirectional"))
      (node (ref "U1") (pin "67") (pinfunction "GND_67") (pintype "bidirectional"))
      (node (ref "U1") (pin "68") (pinfunction "GND_68") (pintype "bidirectional"))
      (node (ref "U1") (pin "7") (pinfunction "GND_7") (pintype "bidirectional"))
      (node (ref "U1") (pin "73") (pinfunction "GND_73") (pintype "bidirectional"))
      (node (ref "U1") (pin "74") (pinfunction "GND_74") (pintype "bidirectional"))
      (node (ref "U1") (pin "79") (pinfunction "GND_79") (pintype "bidirectional"))
      (node (ref "U1") (pin "80") (pinfunction "GND_80") (pintype "bidirectional"))
      (node (ref "U1") (pin "85") (pinfunction "GND_85") (pintype "bidirectional"))
      (node (ref "U1") (pin "86") (pinfunction "GND_86") (pintype "bidirectional"))
      (node (ref "U1") (pin "91") (pinfunction "GND_91") (pintype "bidirectional"))
      (node (ref "U1") (pin "92") (pinfunction "GND_92") (pintype "bidirectional"))
      (node (ref "U1") (pin "97") (pinfunction "GND_97") (pintype "bidirectional"))
      (node (ref "U1") (pin "98") (pinfunction "GND_98") (pintype "bidirectional"))
      (node (ref "U2") (pin "3") (pinfunction "GND_3") (pintype "bidirectional"))
      (node (ref "U2") (pin "6") (pinfunction "GND_6") (pintype "bidirectional"))
      (node (ref "U3") (pin "3") (pinfunction "GND_3") (pintype "bidirectional"))
      (node (ref "U3") (pin "6") (pinfunction "GND_6") (pintype "bidirectional"))
      (node (ref "U4") (pin "3") (pinfunction "GND_3") (pintype "bidirectional"))
      (node (ref "U4") (pin "6") (pinfunction "GND_6") (pintype "bidirectional"))
      (node (ref "U5") (pin "3") (pinfunction "GND_3") (pintype "bidirectional"))
      (node (ref "U5") (pin "6") (pinfunction "GND_6") (pintype "bidirectional"))
      (node (ref "U6") (pin "3") (pinfunction "GND_3") (pintype "bidirectional"))
      (node (ref "U6") (pin "6") (pinfunction "GND_6") (pintype "bidirectional"))
      (node (ref "U7") (pin "1") (pinfunction "ADJ/GND_1") (pintype "input"))
      (node (ref "USB_A") (pin "1") (pinfunction "VSS_1") (pintype "bidirectional"))
      (node (ref "USB_B") (pin "1") (pinfunction "VSS_1") (pintype "bidirectional"))
      (node (ref "USB_C") (pin "1") (pinfunction "VSS_1") (pintype "bidirectional"))
    )
    (net (code "7") (name "GPIO_4") (class "Default")
      (node (ref "J1") (pin "7") (pinfunction "GP4_7") (pintype "bidirectional"))
      (node (ref "U1") (pin "15") (pinfunction "GPIO4_15") (pintype "bidirectional"))
    )
    (net (code "8") (name "GPIO_5") (class "Default")
      (node (ref "J1") (pin "29") (pinfunction "GP5_29") (pintype "bidirectional"))
      (node (ref "U1") (pin "17") (pinfunction "GPIO5_17") (pintype "bidirectional"))
    )
    (net (code "9") (name "GPIO_6") (class "Default")
      (node (ref "J1") (pin "31") (pinfunction "GP6_31") (pintype "bidirectional"))
      (node (ref "U1") (pin "21") (pinfunction "GPIO6_21") (pintype "bidirectional"))
    )
    (net (code "10") (name "GPIO_12") (class "Default")
      (node (ref "J1") (pin "32") (pinfunction "GP12_32") (pintype "bidirectional"))
      (node (ref "U1") (pin "45") (pinfunction "GPIO12_45") (pintype "bidirectional"))
    )
    (net (code "11") (name "GPIO_13") (class "Default")
      (node (ref "J1") (pin "33") (pinfunction "GP13_33") (pintype "bidirectional"))
      (node (ref "U1") (pin "47") (pinfunction "GPIO13_47") (pintype "bidirectional"))
    )
    (net (code "12") (name "GPIO_16") (class "Default")
      (node (ref "J1") (pin "36") (pinfunction "GP16_36") (pintype "bidirectional"))
      (node (ref "U1") (pin "57") (pinfunction "GPIO16_57") (pintype "bidirectional"))
    )
    (net (code "13") (name "GPIO_17") (class "Default")
      (node (ref "J1") (pin "11") (pinfunction "GP17_11") (pintype "bidirectional"))
      (node (ref "U1") (pin "59") (pinfunction "GPIO17_59") (pintype "bidirectional"))
    )
    (net (code "14") (name "GPIO_18") (class "Default")
      (node (ref "J1") (pin "12") (pinfunction "GP18#_12") (pintype "bidirectional"))
      (node (ref "U1") (pin "63") (pinfunction "GPIO18_63") (pintype "bidirectional"))
    )
    (net (code "15") (name "GPIO_19") (class "Default")
      (node (ref "J1") (pin "35") (pinfunction "GP19_35") (pintype "bidirectional"))
      (node (ref "U1") (pin "65") (pinfunction "GPIO19_65") (pintype "bidirectional"))
    )
    (net (code "16") (name "GPIO_20") (class "Default")
      (node (ref "J1") (pin "38") (pinfunction "GP20_38") (pintype "bidirectional"))
      (node (ref "U1") (pin "69") (pinfunction "GPIO20_69") (pintype "bidirectional"))
    )
    (net (code "17") (name "GPIO_21") (class "Default")
      (node (ref "J1") (pin "40") (pinfunction "GP21_40") (pintype "bidirectional"))
      (node (ref "U1") (pin "71") (pinfunction "GPIO21_71") (pintype "bidirectional"))
    )
    (net (code "18") (name "GPIO_22") (class "Default")
      (node (ref "J1") (pin "15") (pinfunction "GP22_15") (pintype "bidirectional"))
      (node (ref "U1") (pin "75") (pinfunction "GPIO22_75") (pintype "bidirectional"))
    )
    (net (code "19") (name "GPIO_23") (class "Default")
      (node (ref "J1") (pin "16") (pinfunction "GP23_16") (pintype "bidirectional"))
      (node (ref "U1") (pin "77") (pinfunction "GPIO23_77") (pintype "bidirectional"))
    )
    (net (code "20") (name "GPIO_24") (class "Default")
      (node (ref "J1") (pin "18") (pinfunction "GP24_18") (pintype "bidirectional"))
      (node (ref "U1") (pin "81") (pinfunction "GPIO24_81") (pintype "bidirectional"))
    )
    (net (code "21") (name "GPIO_25") (class "Default")
      (node (ref "J1") (pin "22") (pinfunction "GP25_22") (pintype "bidirectional"))
      (node (ref "U1") (pin "83") (pinfunction "GPIO25_83") (pintype "bidirectional"))
    )
    (net (code "22") (name "GPIO_26") (class "Default")
      (node (ref "J1") (pin "37") (pinfunction "GP26_37") (pintype "bidirectional"))
      (node (ref "U1") (pin "87") (pinfunction "GPIO26_87") (pintype "bidirectional"))
    )
    (net (code "23") (name "GPIO_27") (class "Default")
      (node (ref "J1") (pin "13") (pinfunction "GP27_13") (pintype "bidirectional"))
      (node (ref "U1") (pin "89") (pinfunction "GPIO27_89") (pintype "bidirectional"))
    )
    (net (code "24") (name "HOST_USB_DM_N") (class "Default")
      (node (ref "U1") (pin "167") (pinfunction "USB_DM_N_167") (pintype "bidirectional"))
      (node (ref "USB_A") (pin "15") (pinfunction "DMU_15") (pintype "bidirectional"))
    )
    (net (code "25") (name "HOST_USB_DP_P") (class "Default")
      (node (ref "U1") (pin "165") (pinfunction "USB_DP_P_165") (pintype "bidirectional"))
      (node (ref "USB_A") (pin "16") (pinfunction "DPU_16") (pintype "bidirectional"))
    )
    (net (code "26") (name "ID_SC") (class "Default")
      (node (ref "J1") (pin "28") (pinfunction "ID_SC_28") (pintype "bidirectional"))
    )
    (net (code "27") (name "ID_SD") (class "Default")
      (node (ref "J1") (pin "27") (pinfunction "ID_SD_27") (pintype "bidirectional"))
    )
    (net (code "28") (name "N$14") (class "Default")
      (node (ref "USB_C") (pin "4") (pinfunction "DM4_4") (pintype "bidirectional"))
    )
    (net (code "29") (name "N$15") (class "Default")
      (node (ref "USB_C") (pin "5") (pinfunction "DP4_5") (pintype "bidirectional"))
    )
    (net (code "30") (name "N$16") (class "Default")
      (node (ref "USB_C") (pin "6") (pinfunction "DM3_6") (pintype "bidirectional"))
    )
    (net (code "31") (name "N$17") (class "Default")
      (node (ref "USB_C") (pin "7") (pinfunction "DP3_7") (pintype "bidirectional"))
    )
    (net (code "32") (name "N$18") (class "Default")
      (node (ref "USB_C") (pin "8") (pinfunction "DM2_8") (pintype "bidirectional"))
    )
    (net (code "33") (name "N$19") (class "Default")
      (node (ref "USB_C") (pin "9") (pinfunction "DP2_9") (pintype "bidirectional"))
    )
    (net (code "34") (name "N$20") (class "Default")
      (node (ref "USB_C") (pin "10") (pinfunction "DM1_10") (pintype "bidirectional"))
    )
    (net (code "35") (name "N$21") (class "Default")
      (node (ref "USB_C") (pin "11") (pinfunction "DP1_11") (pintype "bidirectional"))
    )
    (net (code "36") (name "N$28") (class "Default")
      (node (ref "U1") (pin "3") (pinfunction "GPIO0_3") (pintype "bidirectional"))
    )
    (net (code "37") (name "N$29") (class "Default")
      (node (ref "U1") (pin "5") (pinfunction "GPIO1_5") (pintype "bidirectional"))
    )
    (net (code "38") (name "Net-(C33-Pad2)") (class "Default")
      (node (ref "C33") (pin "2") (pinfunction "2_2") (pintype "passive"))
      (node (ref "R17") (pin "1") (pinfunction "1_1") (pintype "passive"))
      (node (ref "U$12") (pin "7") (pinfunction "7_7") (pintype "bidirectional"))
      (node (ref "Y4") (pin "1") (pinfunction "1_1") (pintype "passive"))
    )
    (net (code "39") (name "Net-(C49-Pad2)") (class "Default")
      (node (ref "C49") (pin "2") (pinfunction "2_2") (pintype "passive"))
      (node (ref "R25") (pin "1") (pinfunction "1_1") (pintype "passive"))
      (node (ref "U$16") (pin "7") (pinfunction "7_7") (pintype "bidirectional"))
      (node (ref "Y5") (pin "1") (pinfunction "1_1") (pintype "passive"))
    )
    (net (code "40") (name "Net-(R7-Pad2)") (class "Default")
      (node (ref "R7") (pin "2") (pinfunction "2_2") (pintype "passive"))
      (node (ref "R9") (pin "1") (pinfunction "1_1") (pintype "passive"))
    )
    (net (code "41") (name "Net-(R15-Pad2)") (class "Default")
      (node (ref "R15") (pin "2") (pinfunction "2_2") (pintype "passive"))
      (node (ref "U$12") (pin "1") (pinfunction "1_1") (pintype "bidirectional"))
    )
    (net (code "42") (name "Net-(R16-Pad2)") (class "Default")
      (node (ref "R16") (pin "2") (pinfunction "2_2") (pintype "passive"))
      (node (ref "R17") (pin "2") (pinfunction "2_2") (pintype "passive"))
      (node (ref "U$12") (pin "6") (pinfunction "6_6") (pintype "bidirectional"))
    )
    (net (code "43") (name "Net-(R18-Pad1)") (class "Default")
      (node (ref "R18") (pin "1") (pinfunction "1_1") (pintype "passive"))
      (node (ref "U$12") (pin "20") (pinfunction "20_20") (pintype "bidirectional"))
    )
    (net (code "44") (name "Net-(R23-Pad2)") (class "Default")
      (node (ref "R23") (pin "2") (pinfunction "2_2") (pintype "passive"))
      (node (ref "U$16") (pin "1") (pinfunction "1_1") (pintype "bidirectional"))
    )
    (net (code "45") (name "Net-(R24-Pad2)") (class "Default")
      (node (ref "R24") (pin "2") (pinfunction "2_2") (pintype "passive"))
      (node (ref "R25") (pin "2") (pinfunction "2_2") (pintype "passive"))
      (node (ref "U$16") (pin "6") (pinfunction "6_6") (pintype "bidirectional"))
    )
    (net (code "46") (name "Net-(R26-Pad1)") (class "Default")
      (node (ref "R26") (pin "1") (pinfunction "1_1") (pintype "passive"))
      (node (ref "U$16") (pin "20") (pinfunction "20_20") (pintype "bidirectional"))
    )
    (net (code "47") (name "Net-(TP_VCORE-1)") (class "Default")
      (node (ref "TP_VCORE") (pin "P$1") (pinfunction "1_P$1") (pintype "bidirectional"))
      (node (ref "U1") (pin "179") (pinfunction "VDD_CORE_179") (pintype "bidirectional"))
    )
    (net (code "48") (name "Net-(U1H-EMMC_DISABLE_N)") (class "Default")
      (node (ref "R14") (pin "1") (pinfunction "1_1") (pintype "passive"))
      (node (ref "U1") (pin "2") (pinfunction "EMMC_DISABLE_N_2") (pintype "bidirectional"))
    )
    (net (code "49") (name "Net-(U1J-USB_OTGID)") (class "Default")
      (node (ref "R11") (pin "2") (pinfunction "2_2") (pintype "passive"))
      (node (ref "U1") (pin "168") (pinfunction "USB_OTGID_168") (pintype "bidirectional"))
    )
    (net (code "50") (name "Net-(U2-ADJUST)") (class "Default")
      (node (ref "R1") (pin "1") (pinfunction "1_1") (pintype "passive"))
      (node (ref "R2") (pin "2") (pinfunction "2_2") (pintype "passive"))
      (node (ref "U2") (pin "5") (pinfunction "ADJUST_5") (pintype "bidirectional"))
    )
    (net (code "51") (name "Net-(U3-ADJUST)") (class "Default")
      (node (ref "R3") (pin "1") (pinfunction "1_1") (pintype "passive"))
      (node (ref "R4") (pin "2") (pinfunction "2_2") (pintype "passive"))
      (node (ref "U3") (pin "5") (pinfunction "ADJUST_5") (pintype "bidirectional"))
    )
    (net (code "52") (name "Net-(U4-ADJUST)") (class "Default")
      (node (ref "R5") (pin "1") (pinfunction "1_1") (pintype "passive"))
      (node (ref "R6") (pin "2") (pinfunction "2_2") (pintype "passive"))
      (node (ref "U4") (pin "5") (pinfunction "ADJUST_5") (pintype "bidirectional"))
    )
    (net (code "53") (name "Net-(U5-ADJUST)") (class "Default")
      (node (ref "R7") (pin "1") (pinfunction "1_1") (pintype "passive"))
      (node (ref "R8") (pin "2") (pinfunction "2_2") (pintype "passive"))
      (node (ref "U5") (pin "5") (pinfunction "ADJUST_5") (pintype "bidirectional"))
    )
    (net (code "54") (name "Net-(U6-ADJUST)") (class "Default")
      (node (ref "R21") (pin "1") (pinfunction "1_1") (pintype "passive"))
      (node (ref "R22") (pin "2") (pinfunction "2_2") (pintype "passive"))
      (node (ref "U6") (pin "5") (pinfunction "ADJUST_5") (pintype "bidirectional"))
    )
    (net (code "55") (name "Net-(USB_A-BUSJ)") (class "Default")
      (node (ref "C18") (pin "+") (pinfunction "+_+") (pintype "passive"))
      (node (ref "C20") (pin "1") (pinfunction "1_1") (pintype "passive"))
      (node (ref "USB_A") (pin "13") (pinfunction "VD33_13") (pintype "bidirectional"))
      (node (ref "USB_A") (pin "17") (pinfunction "XRSTJ_17") (pintype "bidirectional"))
      (node (ref "USB_A") (pin "18") (pinfunction "VBUSM_18") (pintype "bidirectional"))
      (node (ref "USB_A") (pin "19") (pinfunction "BUSJ_19") (pintype "bidirectional"))
      (node (ref "USB_A") (pin "21") (pinfunction "VD33_O_21") (pintype "bidirectional"))
      (node (ref "USB_A") (pin "26") (pinfunction "OVCJ_26") (pintype "bidirectional"))
    )
    (net (code "56") (name "Net-(USB_A-REXT)") (class "Default")
      (node (ref "R10") (pin "2") (pinfunction "2_2") (pintype "passive"))
      (node (ref "USB_A") (pin "14") (pinfunction "REXT_14") (pintype "bidirectional"))
    )
    (net (code "57") (name "Net-(USB_A-VD18)") (class "Default")
      (node (ref "C17") (pin "+") (pinfunction "+_+") (pintype "passive"))
      (node (ref "C19") (pin "1") (pinfunction "1_1") (pintype "passive"))
      (node (ref "USB_A") (pin "12") (pinfunction "VD18_O_12") (pintype "bidirectional"))
      (node (ref "USB_A") (pin "28") (pinfunction "VD18_28") (pintype "bidirectional"))
    )
    (net (code "58") (name "Net-(USB_A-XIN)") (class "Default")
      (node (ref "USB_A") (pin "3") (pinfunction "XIN_3") (pintype "bidirectional"))
      (node (ref "Y1") (pin "1") (pinfunction "1_1") (pintype "passive"))
    )
    (net (code "59") (name "Net-(USB_A-XOUT)") (class "Default")
      (node (ref "USB_A") (pin "2") (pinfunction "XOUT_2") (pintype "bidirectional"))
      (node (ref "Y1") (pin "3") (pinfunction "2_3") (pintype "passive"))
    )
    (net (code "60") (name "Net-(USB_B-BUSJ)") (class "Default")
      (node (ref "C23") (pin "+") (pinfunction "+_+") (pintype "passive"))
      (node (ref "C25") (pin "1") (pinfunction "1_1") (pintype "passive"))
      (node (ref "USB_B") (pin "13") (pinfunction "VD33_13") (pintype "bidirectional"))
      (node (ref "USB_B") (pin "17") (pinfunction "XRSTJ_17") (pintype "bidirectional"))
      (node (ref "USB_B") (pin "18") (pinfunction "VBUSM_18") (pintype "bidirectional"))
      (node (ref "USB_B") (pin "19") (pinfunction "BUSJ_19") (pintype "bidirectional"))
      (node (ref "USB_B") (pin "21") (pinfunction "VD33_O_21") (pintype "bidirectional"))
      (node (ref "USB_B") (pin "26") (pinfunction "OVCJ_26") (pintype "bidirectional"))
    )
    (net (code "61") (name "Net-(USB_B-REXT)") (class "Default")
      (node (ref "R12") (pin "2") (pinfunction "2_2") (pintype "passive"))
      (node (ref "USB_B") (pin "14") (pinfunction "REXT_14") (pintype "bidirectional"))
    )
    (net (code "62") (name "Net-(USB_B-VD18)") (class "Default")
      (node (ref "C22") (pin "+") (pinfunction "+_+") (pintype "passive"))
      (node (ref "C24") (pin "1") (pinfunction "1_1") (pintype "passive"))
      (node (ref "USB_B") (pin "12") (pinfunction "VD18_O_12") (pintype "bidirectional"))
      (node (ref "USB_B") (pin "28") (pinfunction "VD18_28") (pintype "bidirectional"))
    )
    (net (code "63") (name "Net-(USB_B-XIN)") (class "Default")
      (node (ref "USB_B") (pin "3") (pinfunction "XIN_3") (pintype "bidirectional"))
      (node (ref "Y2") (pin "1") (pinfunction "1_1") (pintype "passive"))
    )
    (net (code "64") (name "Net-(USB_B-XOUT)") (class "Default")
      (node (ref "USB_B") (pin "2") (pinfunction "XOUT_2") (pintype "bidirectional"))
      (node (ref "Y2") (pin "3") (pinfunction "2_3") (pintype "passive"))
    )
    (net (code "65") (name "Net-(USB_C-BUSJ)") (class "Default")
      (node (ref "C28") (pin "+") (pinfunction "+_+") (pintype "passive"))
      (node (ref "C30") (pin "1") (pinfunction "1_1") (pintype "passive"))
      (node (ref "USB_C") (pin "13") (pinfunction "VD33_13") (pintype "bidirectional"))
      (node (ref "USB_C") (pin "17") (pinfunction "XRSTJ_17") (pintype "bidirectional"))
      (node (ref "USB_C") (pin "18") (pinfunction "VBUSM_18") (pintype "bidirectional"))
      (node (ref "USB_C") (pin "19") (pinfunction "BUSJ_19") (pintype "bidirectional"))
      (node (ref "USB_C") (pin "21") (pinfunction "VD33_O_21") (pintype "bidirectional"))
      (node (ref "USB_C") (pin "26") (pinfunction "OVCJ_26") (pintype "bidirectional"))
    )
    (net (code "66") (name "Net-(USB_C-REXT)") (class "Default")
      (node (ref "R13") (pin "2") (pinfunction "2_2") (pintype "passive"))
      (node (ref "USB_C") (pin "14") (pinfunction "REXT_14") (pintype "bidirectional"))
    )
    (net (code "67") (name "Net-(USB_C-VD18)") (class "Default")
      (node (ref "C27") (pin "+") (pinfunction "+_+") (pintype "passive"))
      (node (ref "C29") (pin "1") (pinfunction "1_1") (pintype "passive"))
      (node (ref "USB_C") (pin "12") (pinfunction "VD18_O_12") (pintype "bidirectional"))
      (node (ref "USB_C") (pin "28") (pinfunction "VD18_28") (pintype "bidirectional"))
    )
    (net (code "68") (name "Net-(USB_C-XIN)") (class "Default")
      (node (ref "USB_C") (pin "3") (pinfunction "XIN_3") (pintype "bidirectional"))
      (node (ref "Y3") (pin "1") (pinfunction "1_1") (pintype "passive"))
    )
    (net (code "69") (name "Net-(USB_C-XOUT)") (class "Default")
      (node (ref "USB_C") (pin "2") (pinfunction "XOUT_2") (pintype "bidirectional"))
      (node (ref "Y3") (pin "3") (pinfunction "2_3") (pintype "passive"))
    )
    (net (code "70") (name "Net-(Y4-2)") (class "Default")
      (node (ref "C32") (pin "2") (pinfunction "2_2") (pintype "passive"))
      (node (ref "R16") (pin "1") (pinfunction "1_1") (pintype "passive"))
      (node (ref "Y4") (pin "3") (pinfunction "2_3") (pintype "passive"))
    )
    (net (code "71") (name "Net-(Y5-2)") (class "Default")
      (node (ref "C48") (pin "2") (pinfunction "2_2") (pintype "passive"))
      (node (ref "R24") (pin "1") (pinfunction "1_1") (pintype "passive"))
      (node (ref "Y5") (pin "3") (pinfunction "2_3") (pintype "passive"))
    )
    (net (code "72") (name "SATA_1_AGND") (class "Default")
      (node (ref "C32") (pin "1") (pinfunction "1_1") (pintype "passive"))
      (node (ref "C33") (pin "1") (pinfunction "1_1") (pintype "passive"))
      (node (ref "C34") (pin "2") (pinfunction "2_2") (pintype "passive"))
      (node (ref "C35") (pin "2") (pinfunction "2_2") (pintype "passive"))
      (node (ref "C41") (pin "2") (pinfunction "2_2") (pintype "passive"))
      (node (ref "C43") (pin "2") (pinfunction "2_2") (pintype "passive"))
      (node (ref "C44") (pin "2") (pinfunction "2_2") (pintype "passive"))
      (node (ref "R18") (pin "2") (pinfunction "2_2") (pintype "passive"))
      (node (ref "SH1") (pin "2") (pinfunction "P$2_2") (pintype "bidirectional"))
      (node (ref "U$12") (pin "16") (pinfunction "16_16") (pintype "bidirectional"))
      (node (ref "U$12") (pin "21") (pinfunction "21_21") (pintype "bidirectional"))
      (node (ref "U$12") (pin "25") (pinfunction "25_25") (pintype "bidirectional"))
    )
    (net (code "73") (name "SATA_1_CON_RXDN") (class "Default")
      (node (ref "C38") (pin "2") (pinfunction "2_2") (pintype "passive"))
      (node (ref "U$15") (pin "P$5") (pinfunction "RECEIVE-_P$5") (pintype "bidirectional"))
    )
    (net (code "74") (name "SATA_1_CON_RXDP") (class "Default")
      (node (ref "C39") (pin "2") (pinfunction "2_2") (pintype "passive"))
      (node (ref "U$15") (pin "P$6") (pinfunction "RECEIVE+_P$6") (pintype "bidirectional"))
    )
    (net (code "75") (name "SATA_1_CON_TXDN") (class "Default")
      (node (ref "C37") (pin "2") (pinfunction "2_2") (pintype "passive"))
      (node (ref "U$15") (pin "P$3") (pinfunction "TRANSMIT-_P$3") (pintype "bidirectional"))
    )
    (net (code "76") (name "SATA_1_CON_TXDP") (class "Default")
      (node (ref "C36") (pin "2") (pinfunction "2_2") (pintype "passive"))
      (node (ref "U$15") (pin "P$2") (pinfunction "TRANSMIT+_P$2") (pintype "bidirectional"))
    )
    (net (code "77") (name "SATA_1_IC_RXDN") (class "Default")
      (node (ref "C38") (pin "1") (pinfunction "1_1") (pintype "passive"))
      (node (ref "U$12") (pin "24") (pinfunction "24_24") (pintype "bidirectional"))
    )
    (net (code "78") (name "SATA_1_IC_RXDP") (class "Default")
      (node (ref "C39") (pin "1") (pinfunction "1_1") (pintype "passive"))
      (node (ref "U$12") (pin "23") (pinfunction "23_23") (pintype "bidirectional"))
    )
    (net (code "79") (name "SATA_1_IC_TXDN") (class "Default")
      (node (ref "C37") (pin "1") (pinfunction "1_1") (pintype "passive"))
      (node (ref "U$12") (pin "26") (pinfunction "26_26") (pintype "bidirectional"))
    )
    (net (code "80") (name "SATA_1_IC_TXDP") (class "Default")
      (node (ref "C36") (pin "1") (pinfunction "1_1") (pintype "passive"))
      (node (ref "U$12") (pin "27") (pinfunction "27_27") (pintype "bidirectional"))
    )
    (net (code "81") (name "SATA_1_VCC1.2D") (class "Default")
      (node (ref "C34") (pin "1") (pinfunction "1_1") (pintype "passive"))
      (node (ref "C43") (pin "1") (pinfunction "1_1") (pintype "passive"))
      (node (ref "C44") (pin "1") (pinfunction "1_1") (pintype "passive"))
      (node (ref "U$12") (pin "19") (pinfunction "19_19") (pintype "bidirectional"))
      (node (ref "U$12") (pin "28") (pinfunction "28_28") (pintype "bidirectional"))
      (node (ref "U$12") (pin "8") (pinfunction "8_8") (pintype "bidirectional"))
      (node (ref "U$12") (pin "9") (pinfunction "9_9") (pintype "bidirectional"))
    )
    (net (code "82") (name "SATA_1_VCC3.3D") (class "Default")
      (node (ref "C31") (pin "1") (pinfunction "1_1") (pintype "passive"))
      (node (ref "C35") (pin "1") (pinfunction "1_1") (pintype "passive"))
      (node (ref "C40") (pin "1") (pinfunction "1_1") (pintype "passive"))
      (node (ref "C41") (pin "1") (pinfunction "1_1") (pintype "passive"))
      (node (ref "U$12") (pin "13") (pinfunction "13_13") (pintype "bidirectional"))
      (node (ref "U$12") (pin "17") (pinfunction "17_17") (pintype "bidirectional"))
      (node (ref "U$12") (pin "22") (pinfunction "22_22") (pintype "bidirectional"))
      (node (ref "U$12") (pin "5") (pinfunction "5_5") (pintype "bidirectional"))
    )
    (net (code "83") (name "SATA_2_AGND") (class "Default")
      (node (ref "C48") (pin "1") (pinfunction "1_1") (pintype "passive"))
      (node (ref "C49") (pin "1") (pinfunction "1_1") (pintype "passive"))
      (node (ref "R26") (pin "2") (pinfunction "2_2") (pintype "passive"))
      (node (ref "SH2") (pin "2") (pinfunction "P$2_2") (pintype "bidirectional"))
      (node (ref "U$16") (pin "16") (pinfunction "16_16") (pintype "bidirectional"))
      (node (ref "U$16") (pin "21") (pinfunction "21_21") (pintype "bidirectional"))
      (node (ref "U$16") (pin "25") (pinfunction "25_25") (pintype "bidirectional"))
    )
    (net (code "84") (name "SATA_2_CON_RXDN") (class "Default")
      (node (ref "C52") (pin "2") (pinfunction "2_2") (pintype "passive"))
      (node (ref "U$17") (pin "P$5") (pinfunction "RECEIVE-_P$5") (pintype "bidirectional"))
    )
    (net (code "85") (name "SATA_2_CON_RXDP") (class "Default")
      (node (ref "C53") (pin "2") (pinfunction "2_2") (pintype "passive"))
      (node (ref "U$17") (pin "P$6") (pinfunction "RECEIVE+_P$6") (pintype "bidirectional"))
    )
    (net (code "86") (name "SATA_2_CON_TXDN") (class "Default")
      (node (ref "C51") (pin "2") (pinfunction "2_2") (pintype "passive"))
      (node (ref "U$17") (pin "P$3") (pinfunction "TRANSMIT-_P$3") (pintype "bidirectional"))
    )
    (net (code "87") (name "SATA_2_CON_TXDP") (class "Default")
      (node (ref "C50") (pin "2") (pinfunction "2_2") (pintype "passive"))
      (node (ref "U$17") (pin "P$2") (pinfunction "TRANSMIT+_P$2") (pintype "bidirectional"))
    )
    (net (code "88") (name "SATA_2_IC_RXDN") (class "Default")
      (node (ref "C52") (pin "1") (pinfunction "1_1") (pintype "passive"))
      (node (ref "U$16") (pin "24") (pinfunction "24_24") (pintype "bidirectional"))
    )
    (net (code "89") (name "SATA_2_IC_RXDP") (class "Default")
      (node (ref "C53") (pin "1") (pinfunction "1_1") (pintype "passive"))
      (node (ref "U$16") (pin "23") (pinfunction "23_23") (pintype "bidirectional"))
    )
    (net (code "90") (name "SATA_2_IC_TXDN") (class "Default")
      (node (ref "C51") (pin "1") (pinfunction "1_1") (pintype "passive"))
      (node (ref "U$16") (pin "26") (pinfunction "26_26") (pintype "bidirectional"))
    )
    (net (code "91") (name "SATA_2_IC_TXDP") (class "Default")
      (node (ref "C50") (pin "1") (pinfunction "1_1") (pintype "passive"))
      (node (ref "U$16") (pin "27") (pinfunction "27_27") (pintype "bidirectional"))
    )
    (net (code "92") (name "SATA_2_VCC1.2D") (class "Default")
      (node (ref "U$16") (pin "19") (pinfunction "19_19") (pintype "bidirectional"))
      (node (ref "U$16") (pin "28") (pinfunction "28_28") (pintype "bidirectional"))
      (node (ref "U$16") (pin "8") (pinfunction "8_8") (pintype "bidirectional"))
      (node (ref "U$16") (pin "9") (pinfunction "9_9") (pintype "bidirectional"))
    )
    (net (code "93") (name "SATA_2_VCC3.3D") (class "Default")
      (node (ref "U$16") (pin "13") (pinfunction "13_13") (pintype "bidirectional"))
      (node (ref "U$16") (pin "17") (pinfunction "17_17") (pintype "bidirectional"))
      (node (ref "U$16") (pin "22") (pinfunction "22_22") (pintype "bidirectional"))
      (node (ref "U$16") (pin "5") (pinfunction "5_5") (pintype "bidirectional"))
    )
    (net (code "94") (name "SATA_A_3.3V") (class "Default")
      (node (ref "C47") (pin "1") (pinfunction "1_1") (pintype "passive"))
      (node (ref "U$15") (pin "P$10") (pinfunction "3.3V_P$10") (pintype "bidirectional"))
      (node (ref "U$15") (pin "P$8") (pinfunction "3.3V_P$8") (pintype "bidirectional"))
      (node (ref "U$15") (pin "P$9") (pinfunction "3.3V_P$9") (pintype "bidirectional"))
      (node (ref "U$17") (pin "P$10") (pinfunction "3.3V_P$10") (pintype "bidirectional"))
      (node (ref "U$17") (pin "P$8") (pinfunction "3.3V_P$8") (pintype "bidirectional"))
      (node (ref "U$17") (pin "P$9") (pinfunction "3.3V_P$9") (pintype "bidirectional"))
      (node (ref "U7") (pin "2") (pinfunction "OUTPUT_2_2") (pintype "output"))
      (node (ref "U7") (pin "4") (pinfunction "OUTPUT_4") (pintype "output"))
    )
    (net (code "95") (name "SATA_A_5V") (class "Default")
      (node (ref "C45") (pin "1") (pinfunction "1_1") (pintype "passive"))
      (node (ref "R21") (pin "2") (pinfunction "2_2") (pintype "passive"))
      (node (ref "U$15") (pin "P$14") (pinfunction "5V_P$14") (pintype "bidirectional"))
      (node (ref "U$15") (pin "P$15") (pinfunction "5V_P$15") (pintype "bidirectional"))
      (node (ref "U$15") (pin "P$16") (pinfunction "5V_P$16") (pintype "bidirectional"))
      (node (ref "U$17") (pin "P$14") (pinfunction "5V_P$14") (pintype "bidirectional"))
      (node (ref "U$17") (pin "P$15") (pinfunction "5V_P$15") (pintype "bidirectional"))
      (node (ref "U$17") (pin "P$16") (pinfunction "5V_P$16") (pintype "bidirectional"))
      (node (ref "U6") (pin "4") (pinfunction "VOUT_4") (pintype "bidirectional"))
      (node (ref "U7") (pin "3") (pinfunction "INPUT_3") (pintype "input"))
    )
    (net (code "96") (name "SCL1_I2C") (class "Default")
      (node (ref "J1") (pin "5") (pinfunction "SCL_5") (pintype "bidirectional"))
      (node (ref "U1") (pin "11") (pinfunction "GPIO3_11") (pintype "bidirectional"))
    )
    (net (code "97") (name "SDA1_I2C") (class "Default")
      (node (ref "J1") (pin "3") (pinfunction "SDA_3") (pintype "bidirectional"))
      (node (ref "U1") (pin "9") (pinfunction "GPIO2_9") (pintype "bidirectional"))
    )
    (net (code "98") (name "SPI0_MISO") (class "Default")
      (node (ref "J1") (pin "21") (pinfunction "MISO_21") (pintype "input"))
      (node (ref "U1") (pin "29") (pinfunction "GPIO9_29") (pintype "bidirectional"))
    )
    (net (code "99") (name "SPI0_MOSI") (class "Default")
      (node (ref "J1") (pin "19") (pinfunction "MOSI_19") (pintype "output"))
      (node (ref "U1") (pin "33") (pinfunction "GPIO10_33") (pintype "bidirectional"))
    )
    (net (code "100") (name "SPI0_SCLK") (class "Default")
      (node (ref "J1") (pin "23") (pinfunction "SCLK_23") (pintype "output"))
      (node (ref "U1") (pin "35") (pinfunction "GPIO11_35") (pintype "bidirectional"))
    )
    (net (code "101") (name "SPIO_CE0_N") (class "Default")
      (node (ref "J1") (pin "24") (pinfunction "CE0_24") (pintype "output"))
      (node (ref "U1") (pin "27") (pinfunction "GPIO8_27") (pintype "bidirectional"))
    )
    (net (code "102") (name "SPIO_CE1_N") (class "Default")
      (node (ref "J1") (pin "26") (pinfunction "CE1_26") (pintype "output"))
      (node (ref "U1") (pin "23") (pinfunction "GPIO7_23") (pintype "bidirectional"))
    )
    (net (code "103") (name "UART0_RXD") (class "Default")
      (node (ref "J1") (pin "10") (pinfunction "RXI_10") (pintype "input"))
      (node (ref "U1") (pin "53") (pinfunction "GPIO15_53") (pintype "bidirectional"))
    )
    (net (code "104") (name "UART0_TXD") (class "Default")
      (node (ref "J1") (pin "8") (pinfunction "TXO_8") (pintype "output"))
      (node (ref "U1") (pin "51") (pinfunction "GPIO14_51") (pintype "bidirectional"))
    )
    (net (code "105") (name "USB_A1_M") (class "Default")
      (node (ref "USB_A") (pin "10") (pinfunction "DM1_10") (pintype "bidirectional"))
      (node (ref "USB_B") (pin "15") (pinfunction "DMU_15") (pintype "bidirectional"))
    )
    (net (code "106") (name "USB_A1_P") (class "Default")
      (node (ref "USB_A") (pin "11") (pinfunction "DP1_11") (pintype "bidirectional"))
      (node (ref "USB_B") (pin "16") (pinfunction "DPU_16") (pintype "bidirectional"))
    )
    (net (code "107") (name "USB_A2_M") (class "Default")
      (node (ref "USB_A") (pin "8") (pinfunction "DM2_8") (pintype "bidirectional"))
      (node (ref "USB_C") (pin "15") (pinfunction "DMU_15") (pintype "bidirectional"))
    )
    (net (code "108") (name "USB_A2_P") (class "Default")
      (node (ref "USB_A") (pin "9") (pinfunction "DP2_9") (pintype "bidirectional"))
      (node (ref "USB_C") (pin "16") (pinfunction "DPU_16") (pintype "bidirectional"))
    )
    (net (code "109") (name "USB_A3_M") (class "Default")
      (node (ref "USB_A") (pin "6") (pinfunction "DM3_6") (pintype "bidirectional"))
    )
    (net (code "110") (name "USB_A3_P") (class "Default")
      (node (ref "USB_A") (pin "7") (pinfunction "DP3_7") (pintype "bidirectional"))
    )
    (net (code "111") (name "USB_A4_M") (class "Default")
      (node (ref "USB_A") (pin "4") (pinfunction "DM4_4") (pintype "bidirectional"))
    )
    (net (code "112") (name "USB_A4_P") (class "Default")
      (node (ref "USB_A") (pin "5") (pinfunction "DP4_5") (pintype "bidirectional"))
    )
    (net (code "113") (name "USB_B2_M") (class "Default")
      (node (ref "U$12") (pin "4") (pinfunction "4_4") (pintype "bidirectional"))
      (node (ref "U$16") (pin "4") (pinfunction "4_4") (pintype "bidirectional"))
      (node (ref "USB_B") (pin "10") (pinfunction "DM1_10") (pintype "bidirectional"))
      (node (ref "USB_B") (pin "8") (pinfunction "DM2_8") (pintype "bidirectional"))
    )
    (net (code "114") (name "USB_B2_P") (class "Default")
      (node (ref "U$12") (pin "3") (pinfunction "3_3") (pintype "bidirectional"))
      (node (ref "U$16") (pin "3") (pinfunction "3_3") (pintype "bidirectional"))
      (node (ref "USB_B") (pin "11") (pinfunction "DP1_11") (pintype "bidirectional"))
      (node (ref "USB_B") (pin "9") (pinfunction "DP2_9") (pintype "bidirectional"))
    )
    (net (code "115") (name "USB_B3_M") (class "Default")
      (node (ref "USB_B") (pin "6") (pinfunction "DM3_6") (pintype "bidirectional"))
    )
    (net (code "116") (name "USB_B3_P") (class "Default")
      (node (ref "USB_B") (pin "7") (pinfunction "DP3_7") (pintype "bidirectional"))
    )
    (net (code "117") (name "USB_B4_M") (class "Default")
      (node (ref "USB_B") (pin "4") (pinfunction "DM4_4") (pintype "bidirectional"))
    )
    (net (code "118") (name "USB_B4_P") (class "Default")
      (node (ref "USB_B") (pin "5") (pinfunction "DP4_5") (pintype "bidirectional"))
    )
    (net (code "119") (name "USB_VBUS") (class "Default")
      (node (ref "R19") (pin "2") (pinfunction "2_2") (pintype "passive"))
      (node (ref "R20") (pin "2") (pinfunction "2_2") (pintype "passive"))
      (node (ref "U$12") (pin "10") (pinfunction "10_10") (pintype "bidirectional"))
      (node (ref "U$16") (pin "10") (pinfunction "10_10") (pintype "bidirectional"))
    )
    (net (code "120") (name "unconnected-(U$12-Pad11)") (class "Default")
      (node (ref "U$12") (pin "11") (pinfunction "11_11") (pintype "bidirectional"))
    )
    (net (code "121") (name "unconnected-(U$12-Pad12)") (class "Default")
      (node (ref "U$12") (pin "12") (pinfunction "12_12") (pintype "bidirectional"))
    )
    (net (code "122") (name "unconnected-(U$12-Pad14)") (class "Default")
      (node (ref "U$12") (pin "14") (pinfunction "14_14") (pintype "bidirectional"))
    )
    (net (code "123") (name "unconnected-(U$12-Pad15)") (class "Default")
      (node (ref "U$12") (pin "15") (pinfunction "15_15") (pintype "bidirectional"))
    )
    (net (code "124") (name "unconnected-(U$16-Pad11)") (class "Default")
      (node (ref "U$16") (pin "11") (pinfunction "11_11") (pintype "bidirectional"))
    )
    (net (code "125") (name "unconnected-(U$16-Pad12)") (class "Default")
      (node (ref "U$16") (pin "12") (pinfunction "12_12") (pintype "bidirectional"))
    )
    (net (code "126") (name "unconnected-(U$16-Pad14)") (class "Default")
      (node (ref "U$16") (pin "14") (pinfunction "14_14") (pintype "bidirectional"))
    )
    (net (code "127") (name "unconnected-(U$16-Pad15)") (class "Default")
      (node (ref "U$16") (pin "15") (pinfunction "15_15") (pintype "bidirectional"))
    )
    (net (code "128") (name "unconnected-(U1A-CAM0_C_N-Pad144)") (class "Default")
      (node (ref "U1") (pin "144") (pinfunction "CAM0_C_N_144") (pintype "bidirectional"))
    )
    (net (code "129") (name "unconnected-(U1A-CAM0_C_P-Pad142)") (class "Default")
      (node (ref "U1") (pin "142") (pinfunction "CAM0_C_P_142") (pintype "bidirectional"))
    )
    (net (code "130") (name "unconnected-(U1A-CAM0_D0_N-Pad138)") (class "Default")
      (node (ref "U1") (pin "138") (pinfunction "CAM0_D0_N_138") (pintype "bidirectional"))
    )
    (net (code "131") (name "unconnected-(U1A-CAM0_D0_P-Pad136)") (class "Default")
      (node (ref "U1") (pin "136") (pinfunction "CAM0_D0_P_136") (pintype "bidirectional"))
    )
    (net (code "132") (name "unconnected-(U1A-CAM0_D1_N-Pad150)") (class "Default")
      (node (ref "U1") (pin "150") (pinfunction "CAM0_D1_N_150") (pintype "bidirectional"))
    )
    (net (code "133") (name "unconnected-(U1A-CAM0_D1_P-Pad148)") (class "Default")
      (node (ref "U1") (pin "148") (pinfunction "CAM0_D1_P_148") (pintype "bidirectional"))
    )
    (net (code "134") (name "unconnected-(U1A-CAM1_C_N-Pad149)") (class "Default")
      (node (ref "U1") (pin "149") (pinfunction "CAM1_C_N_149") (pintype "bidirectional"))
    )
    (net (code "135") (name "unconnected-(U1A-CAM1_C_P-Pad147)") (class "Default")
      (node (ref "U1") (pin "147") (pinfunction "CAM1_C_P_147") (pintype "bidirectional"))
    )
    (net (code "136") (name "unconnected-(U1A-CAM1_D0_N-Pad161)") (class "Default")
      (node (ref "U1") (pin "161") (pinfunction "CAM1_D0_N_161") (pintype "bidirectional"))
    )
    (net (code "137") (name "unconnected-(U1A-CAM1_D0_P-Pad159)") (class "Default")
      (node (ref "U1") (pin "159") (pinfunction "CAM1_D0_P_159") (pintype "bidirectional"))
    )
    (net (code "138") (name "unconnected-(U1A-CAM1_D1_N-Pad155)") (class "Default")
      (node (ref "U1") (pin "155") (pinfunction "CAM1_D1_N_155") (pintype "bidirectional"))
    )
    (net (code "139") (name "unconnected-(U1A-CAM1_D1_P-Pad153)") (class "Default")
      (node (ref "U1") (pin "153") (pinfunction "CAM1_D1_P_153") (pintype "bidirectional"))
    )
    (net (code "140") (name "unconnected-(U1A-CAM1_D2_N-Pad143)") (class "Default")
      (node (ref "U1") (pin "143") (pinfunction "CAM1_D2_N_143") (pintype "bidirectional"))
    )
    (net (code "141") (name "unconnected-(U1A-CAM1_D2_P-Pad141)") (class "Default")
      (node (ref "U1") (pin "141") (pinfunction "CAM1_D2_P_141") (pintype "bidirectional"))
    )
    (net (code "142") (name "unconnected-(U1A-CAM1_D3_N-Pad137)") (class "Default")
      (node (ref "U1") (pin "137") (pinfunction "CAM1_D3_N_137") (pintype "bidirectional"))
    )
    (net (code "143") (name "unconnected-(U1A-CAM1_D3_P-Pad135)") (class "Default")
      (node (ref "U1") (pin "135") (pinfunction "CAM1_D3_P_135") (pintype "bidirectional"))
    )
    (net (code "144") (name "unconnected-(U1B-DSI0_C_N-Pad105)") (class "Default")
      (node (ref "U1") (pin "105") (pinfunction "DSI0_C_N_105") (pintype "bidirectional"))
    )
    (net (code "145") (name "unconnected-(U1B-DSI0_C_P-Pad107)") (class "Default")
      (node (ref "U1") (pin "107") (pinfunction "DSI0_C_P_107") (pintype "bidirectional"))
    )
    (net (code "146") (name "unconnected-(U1B-DSI0_D0_N-Pad99)") (class "Default")
      (node (ref "U1") (pin "99") (pinfunction "DSI0_D0_N_99") (pintype "bidirectional"))
    )
    (net (code "147") (name "unconnected-(U1B-DSI0_D0_P-Pad101)") (class "Default")
      (node (ref "U1") (pin "101") (pinfunction "DSI0_D0_P_101") (pintype "bidirectional"))
    )
    (net (code "148") (name "unconnected-(U1B-DSI0_D1_N-Pad93)") (class "Default")
      (node (ref "U1") (pin "93") (pinfunction "DSI0_D1_N_93") (pintype "bidirectional"))
    )
    (net (code "149") (name "unconnected-(U1B-DSI0_D1_P-Pad95)") (class "Default")
      (node (ref "U1") (pin "95") (pinfunction "DSI0_D1_P_95") (pintype "bidirectional"))
    )
    (net (code "150") (name "unconnected-(U1B-DSI1_C_N-Pad102)") (class "Default")
      (node (ref "U1") (pin "102") (pinfunction "DSI1_C_N_102") (pintype "bidirectional"))
    )
    (net (code "151") (name "unconnected-(U1B-DSI1_C_P-Pad100)") (class "Default")
      (node (ref "U1") (pin "100") (pinfunction "DSI1_C_P_100") (pintype "bidirectional"))
    )
    (net (code "152") (name "unconnected-(U1B-DSI1_D0_N-Pad96)") (class "Default")
      (node (ref "U1") (pin "96") (pinfunction "DSI1_D0_N_96") (pintype "bidirectional"))
    )
    (net (code "153") (name "unconnected-(U1B-DSI1_D0_P-Pad94)") (class "Default")
      (node (ref "U1") (pin "94") (pinfunction "DSI1_D0_P_94") (pintype "bidirectional"))
    )
    (net (code "154") (name "unconnected-(U1B-DSI1_D1_N-Pad120)") (class "Default")
      (node (ref "U1") (pin "120") (pinfunction "DSI1_D1_N_120") (pintype "bidirectional"))
    )
    (net (code "155") (name "unconnected-(U1B-DSI1_D1_P-Pad118)") (class "Default")
      (node (ref "U1") (pin "118") (pinfunction "DSI1_D1_P_118") (pintype "bidirectional"))
    )
    (net (code "156") (name "unconnected-(U1B-DSI1_D2_N-Pad114)") (class "Default")
      (node (ref "U1") (pin "114") (pinfunction "DSI1_D2_N_114") (pintype "bidirectional"))
    )
    (net (code "157") (name "unconnected-(U1B-DSI1_D2_P-Pad112)") (class "Default")
      (node (ref "U1") (pin "112") (pinfunction "DSI1_D2_P_112") (pintype "bidirectional"))
    )
    (net (code "158") (name "unconnected-(U1B-DSI1_D3_N-Pad108)") (class "Default")
      (node (ref "U1") (pin "108") (pinfunction "DSI1_D3_N_108") (pintype "bidirectional"))
    )
    (net (code "159") (name "unconnected-(U1B-DSI1_D3_P-Pad106)") (class "Default")
      (node (ref "U1") (pin "106") (pinfunction "DSI1_D3_P_106") (pintype "bidirectional"))
    )
    (net (code "160") (name "unconnected-(U1D-GPIO28-Pad28)") (class "Default")
      (node (ref "U1") (pin "28") (pinfunction "GPIO28_28") (pintype "bidirectional"))
    )
    (net (code "161") (name "unconnected-(U1D-GPIO29-Pad30)") (class "Default")
      (node (ref "U1") (pin "30") (pinfunction "GPIO29_30") (pintype "bidirectional"))
    )
    (net (code "162") (name "unconnected-(U1D-GPIO30-Pad34)") (class "Default")
      (node (ref "U1") (pin "34") (pinfunction "GPIO30_34") (pintype "bidirectional"))
    )
    (net (code "163") (name "unconnected-(U1D-GPIO31-Pad36)") (class "Default")
      (node (ref "U1") (pin "36") (pinfunction "GPIO31_36") (pintype "bidirectional"))
    )
    (net (code "164") (name "unconnected-(U1D-GPIO32-Pad46)") (class "Default")
      (node (ref "U1") (pin "46") (pinfunction "GPIO32_46") (pintype "bidirectional"))
    )
    (net (code "165") (name "unconnected-(U1D-GPIO33-Pad48)") (class "Default")
      (node (ref "U1") (pin "48") (pinfunction "GPIO33_48") (pintype "bidirectional"))
    )
    (net (code "166") (name "unconnected-(U1D-GPIO34-Pad52)") (class "Default")
      (node (ref "U1") (pin "52") (pinfunction "GPIO34_52") (pintype "bidirectional"))
    )
    (net (code "167") (name "unconnected-(U1D-GPIO35-Pad54)") (class "Default")
      (node (ref "U1") (pin "54") (pinfunction "GPIO35_54") (pintype "bidirectional"))
    )
    (net (code "168") (name "unconnected-(U1D-GPIO36-Pad58)") (class "Default")
      (node (ref "U1") (pin "58") (pinfunction "GPIO36_58") (pintype "bidirectional"))
    )
    (net (code "169") (name "unconnected-(U1D-GPIO37-Pad60)") (class "Default")
      (node (ref "U1") (pin "60") (pinfunction "GPIO37_60") (pintype "bidirectional"))
    )
    (net (code "170") (name "unconnected-(U1D-GPIO38-Pad64)") (class "Default")
      (node (ref "U1") (pin "64") (pinfunction "GPIO38_64") (pintype "bidirectional"))
    )
    (net (code "171") (name "unconnected-(U1D-GPIO39-Pad66)") (class "Default")
      (node (ref "U1") (pin "66") (pinfunction "GPIO39_66") (pintype "bidirectional"))
    )
    (net (code "172") (name "unconnected-(U1D-GPIO40-Pad70)") (class "Default")
      (node (ref "U1") (pin "70") (pinfunction "GPIO40_70") (pintype "bidirectional"))
    )
    (net (code "173") (name "unconnected-(U1D-GPIO41-Pad72)") (class "Default")
      (node (ref "U1") (pin "72") (pinfunction "GPIO41_72") (pintype "bidirectional"))
    )
    (net (code "174") (name "unconnected-(U1D-GPIO42-Pad76)") (class "Default")
      (node (ref "U1") (pin "76") (pinfunction "GPIO42_76") (pintype "bidirectional"))
    )
    (net (code "175") (name "unconnected-(U1D-GPIO43-Pad78)") (class "Default")
      (node (ref "U1") (pin "78") (pinfunction "GPIO43_78") (pintype "bidirectional"))
    )
    (net (code "176") (name "unconnected-(U1D-GPIO44-Pad82)") (class "Default")
      (node (ref "U1") (pin "82") (pinfunction "GPIO44_82") (pintype "bidirectional"))
    )
    (net (code "177") (name "unconnected-(U1D-GPIO45-Pad84)") (class "Default")
      (node (ref "U1") (pin "84") (pinfunction "GPIO45_84") (pintype "bidirectional"))
    )
    (net (code "178") (name "unconnected-(U1D-GPIO46_1V8-Pad88)") (class "Default")
      (node (ref "U1") (pin "88") (pinfunction "GPIO46_1V8_88") (pintype "bidirectional"))
    )
    (net (code "179") (name "unconnected-(U1D-GPIO47_1V8-Pad90)") (class "Default")
      (node (ref "U1") (pin "90") (pinfunction "GPIO47_1V8_90") (pintype "bidirectional"))
    )
    (net (code "180") (name "unconnected-(U1E-HDMI_CEC-Pad171)") (class "Default")
      (node (ref "U1") (pin "171") (pinfunction "HDMI_CEC_171") (pintype "bidirectional"))
    )
    (net (code "181") (name "unconnected-(U1E-HDMI_CK_N-Pad111)") (class "Default")
      (node (ref "U1") (pin "111") (pinfunction "HDMI_CK_N_111") (pintype "bidirectional"))
    )
    (net (code "182") (name "unconnected-(U1E-HDMI_CK_P-Pad113)") (class "Default")
      (node (ref "U1") (pin "113") (pinfunction "HDMI_CK_P_113") (pintype "bidirectional"))
    )
    (net (code "183") (name "unconnected-(U1E-HDMI_D0_N-Pad117)") (class "Default")
      (node (ref "U1") (pin "117") (pinfunction "HDMI_D0_N_117") (pintype "bidirectional"))
    )
    (net (code "184") (name "unconnected-(U1E-HDMI_D0_P-Pad119)") (class "Default")
      (node (ref "U1") (pin "119") (pinfunction "HDMI_D0_P_119") (pintype "bidirectional"))
    )
    (net (code "185") (name "unconnected-(U1E-HDMI_D1_N-Pad123)") (class "Default")
      (node (ref "U1") (pin "123") (pinfunction "HDMI_D1_N_123") (pintype "bidirectional"))
    )
    (net (code "186") (name "unconnected-(U1E-HDMI_D1_P-Pad125)") (class "Default")
      (node (ref "U1") (pin "125") (pinfunction "HDMI_D1_P_125") (pintype "bidirectional"))
    )
    (net (code "187") (name "unconnected-(U1E-HDMI_D2_N-Pad129)") (class "Default")
      (node (ref "U1") (pin "129") (pinfunction "HDMI_D2_N_129") (pintype "bidirectional"))
    )
    (net (code "188") (name "unconnected-(U1E-HDMI_D2_P-Pad131)") (class "Default")
      (node (ref "U1") (pin "131") (pinfunction "HDMI_D2_P_131") (pintype "bidirectional"))
    )
    (net (code "189") (name "unconnected-(U1E-HDMI_SCL-Pad175)") (class "Default")
      (node (ref "U1") (pin "175") (pinfunction "HDMI_SCL_175") (pintype "bidirectional"))
    )
    (net (code "190") (name "unconnected-(U1E-HDMI_SDA-Pad173)") (class "Default")
      (node (ref "U1") (pin "173") (pinfunction "HDMI_SDA_173") (pintype "bidirectional"))
    )
    (net (code "191") (name "unconnected-(U1F-VC_TCK-Pad180)") (class "Default")
      (node (ref "U1") (pin "180") (pinfunction "VC_TCK_180") (pintype "bidirectional"))
    )
    (net (code "192") (name "unconnected-(U1F-VC_TDI-Pad174)") (class "Default")
      (node (ref "U1") (pin "174") (pinfunction "VC_TDI_174") (pintype "bidirectional"))
    )
    (net (code "193") (name "unconnected-(U1F-VC_TDO-Pad178)") (class "Default")
      (node (ref "U1") (pin "178") (pinfunction "VC_TDO_178") (pintype "bidirectional"))
    )
    (net (code "194") (name "unconnected-(U1F-VC_TMS-Pad176)") (class "Default")
      (node (ref "U1") (pin "176") (pinfunction "VC_TMS_176") (pintype "bidirectional"))
    )
    (net (code "195") (name "unconnected-(U1F-VC_TSRT_N-Pad172)") (class "Default")
      (node (ref "U1") (pin "172") (pinfunction "VC_TSRT_N_172") (pintype "bidirectional"))
    )
    (net (code "196") (name "unconnected-(U1H-RUN-Pad177)") (class "Default")
      (node (ref "U1") (pin "177") (pinfunction "RUN_177") (pintype "bidirectional"))
    )
    (net (code "197") (name "unconnected-(U1I-TVDAC-Pad166)") (class "Default")
      (node (ref "U1") (pin "166") (pinfunction "TVDAC_166") (pintype "bidirectional"))
    )
    (net (code "198") (name "unconnected-(USB_A-DRV-Pad22)") (class "Default")
      (node (ref "USB_A") (pin "22") (pinfunction "DRV_22") (pintype "bidirectional"))
    )
    (net (code "199") (name "unconnected-(USB_A-LED1-Pad23)") (class "Default")
      (node (ref "USB_A") (pin "23") (pinfunction "LED1_23") (pintype "bidirectional"))
    )
    (net (code "200") (name "unconnected-(USB_A-LED2-Pad24)") (class "Default")
      (node (ref "USB_A") (pin "24") (pinfunction "LED2_24") (pintype "bidirectional"))
    )
    (net (code "201") (name "unconnected-(USB_A-PWRJ-Pad25)") (class "Default")
      (node (ref "USB_A") (pin "25") (pinfunction "PWRJ_25") (pintype "bidirectional"))
    )
    (net (code "202") (name "unconnected-(USB_A-TESTJ-Pad27)") (class "Default")
      (node (ref "USB_A") (pin "27") (pinfunction "TESTJ_27") (pintype "bidirectional"))
    )
    (net (code "203") (name "unconnected-(USB_B-DRV-Pad22)") (class "Default")
      (node (ref "USB_B") (pin "22") (pinfunction "DRV_22") (pintype "bidirectional"))
    )
    (net (code "204") (name "unconnected-(USB_B-LED1-Pad23)") (class "Default")
      (node (ref "USB_B") (pin "23") (pinfunction "LED1_23") (pintype "bidirectional"))
    )
    (net (code "205") (name "unconnected-(USB_B-LED2-Pad24)") (class "Default")
      (node (ref "USB_B") (pin "24") (pinfunction "LED2_24") (pintype "bidirectional"))
    )
    (net (code "206") (name "unconnected-(USB_B-PWRJ-Pad25)") (class "Default")
      (node (ref "USB_B") (pin "25") (pinfunction "PWRJ_25") (pintype "bidirectional"))
    )
    (net (code "207") (name "unconnected-(USB_B-TESTJ-Pad27)") (class "Default")
      (node (ref "USB_B") (pin "27") (pinfunction "TESTJ_27") (pintype "bidirectional"))
    )
    (net (code "208") (name "unconnected-(USB_C-DRV-Pad22)") (class "Default")
      (node (ref "USB_C") (pin "22") (pinfunction "DRV_22") (pintype "bidirectional"))
    )
    (net (code "209") (name "unconnected-(USB_C-LED1-Pad23)") (class "Default")
      (node (ref "USB_C") (pin "23") (pinfunction "LED1_23") (pintype "bidirectional"))
    )
    (net (code "210") (name "unconnected-(USB_C-LED2-Pad24)") (class "Default")
      (node (ref "USB_C") (pin "24") (pinfunction "LED2_24") (pintype "bidirectional"))
    )
    (net (code "211") (name "unconnected-(USB_C-PWRJ-Pad25)") (class "Default")
      (node (ref "USB_C") (pin "25") (pinfunction "PWRJ_25") (pintype "bidirectional"))
    )
    (net (code "212") (name "unconnected-(USB_C-TESTJ-Pad27)") (class "Default")
      (node (ref "USB_C") (pin "27") (pinfunction "TESTJ_27") (pintype "bidirectional"))
    )
  )
)
